# audio_chip_v2.net
KiCad netlist of a schematic drawn in EasyEDA
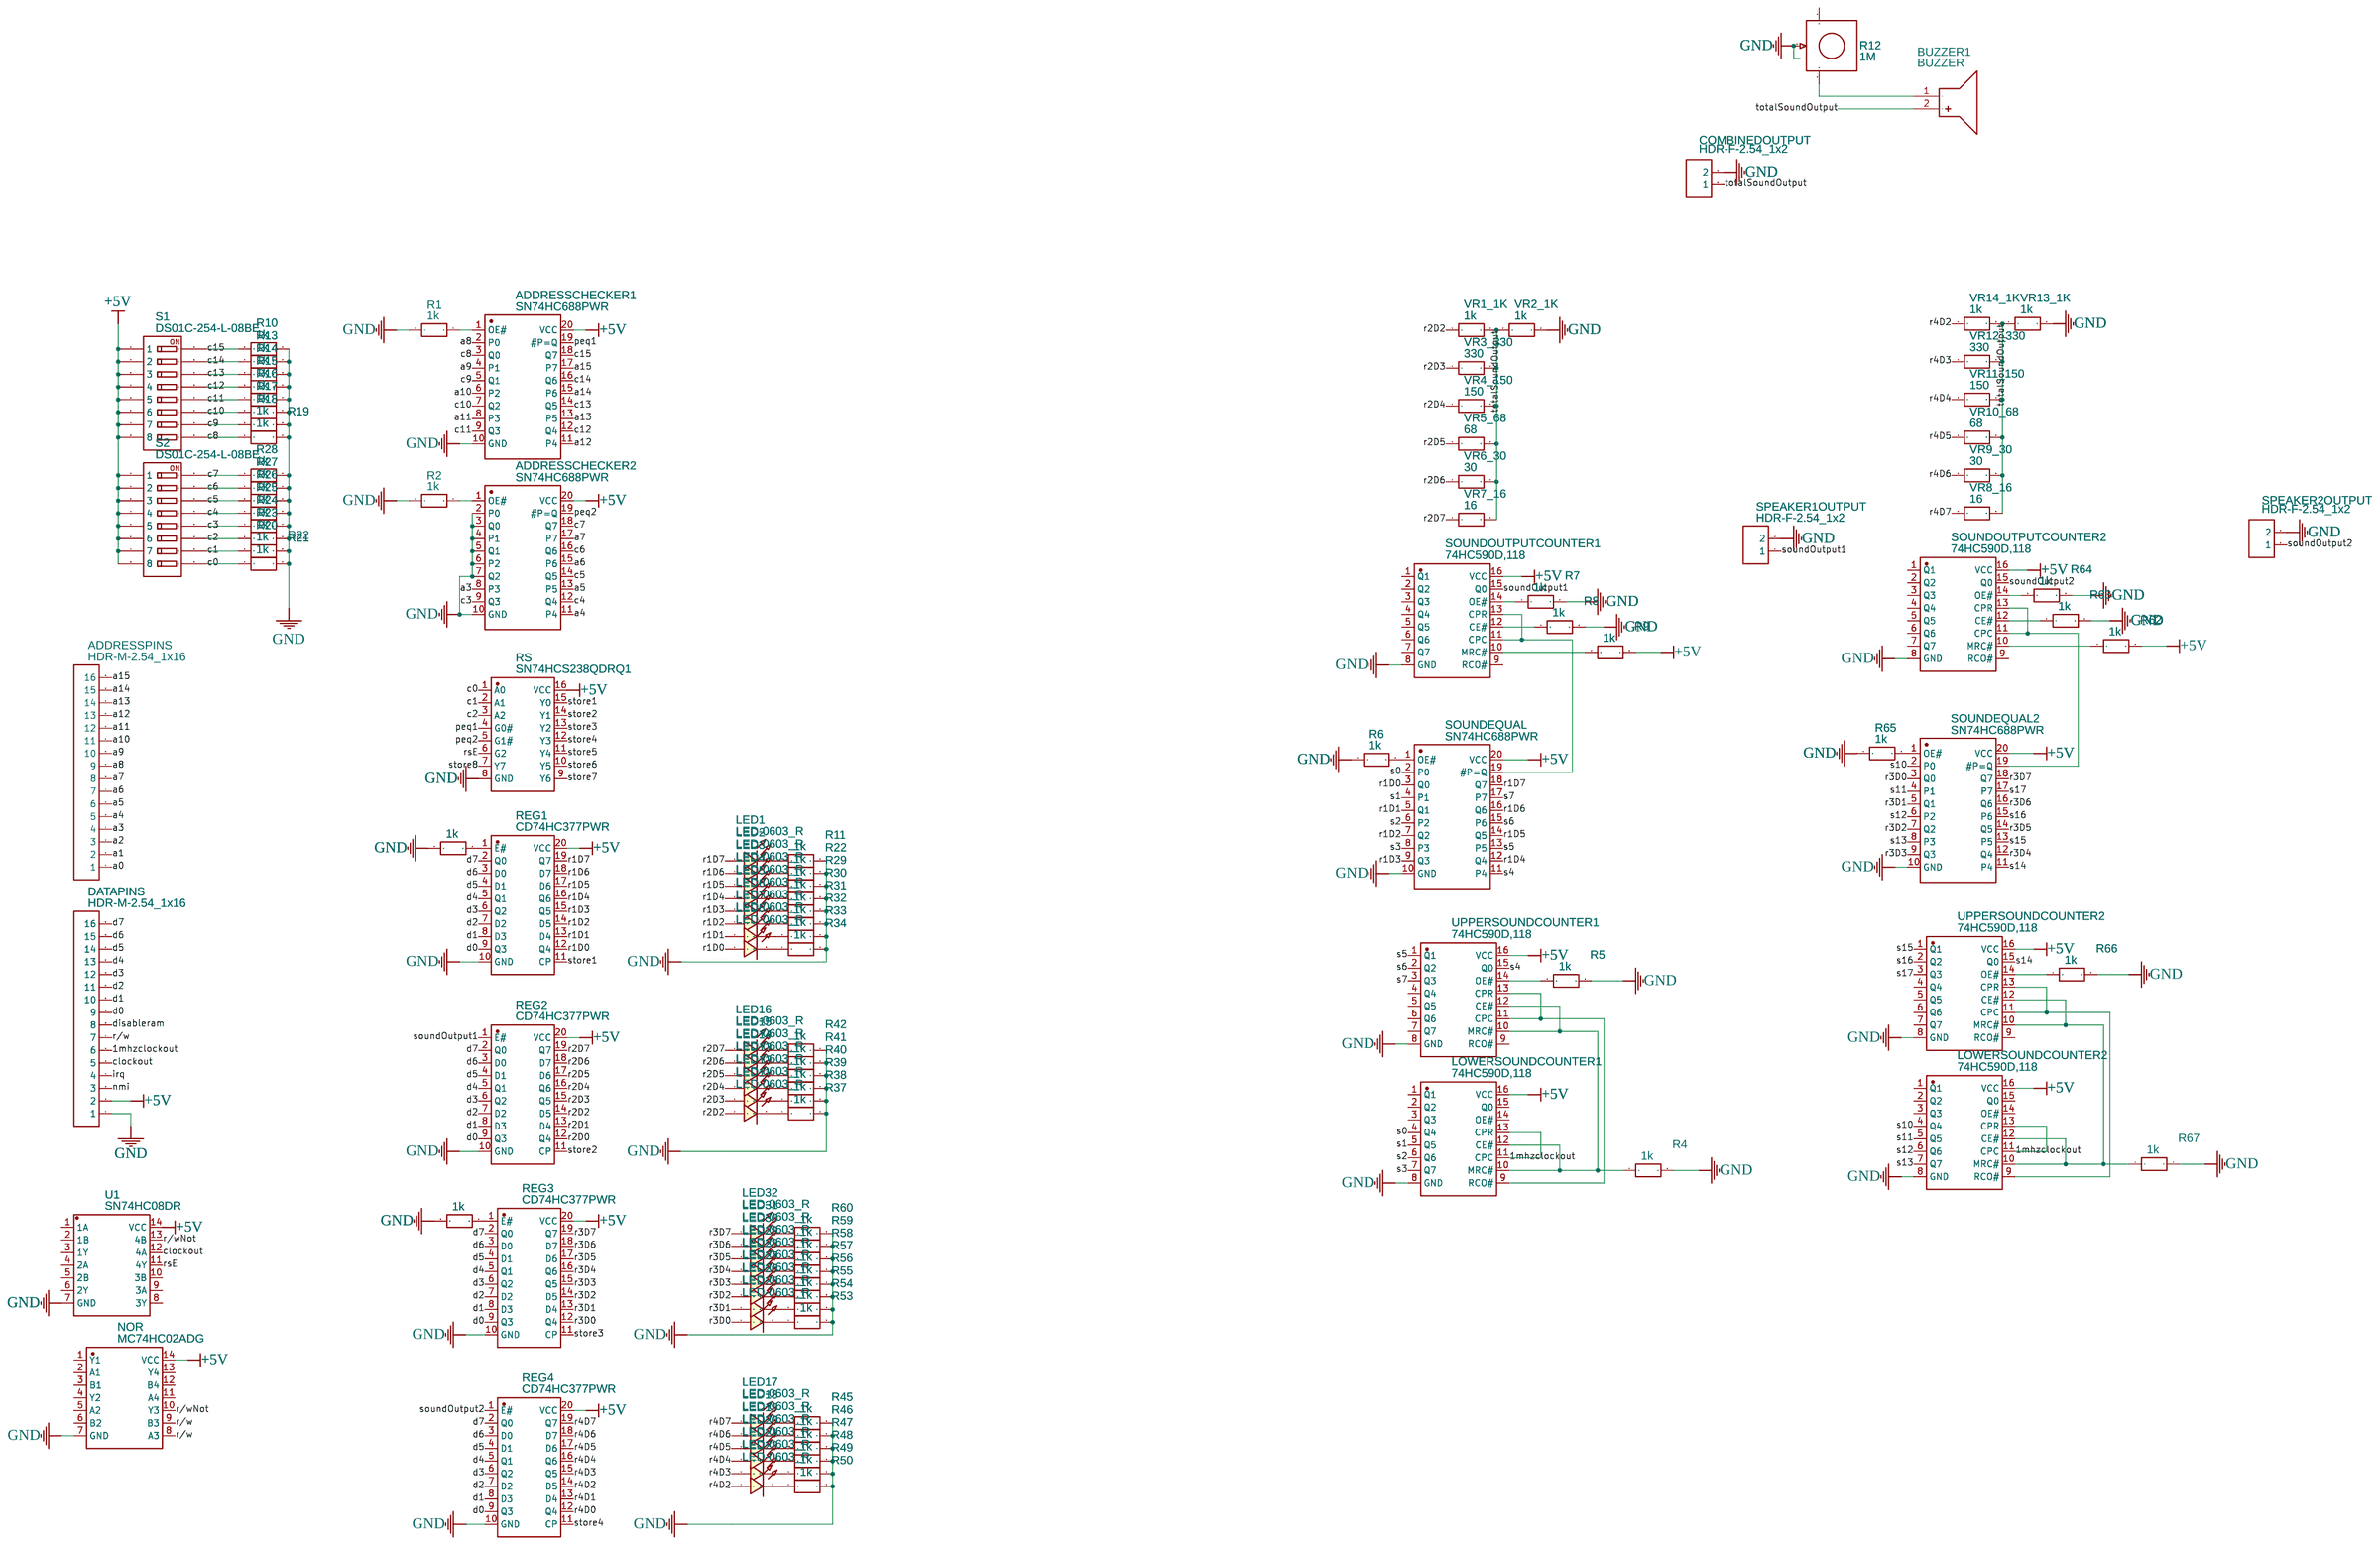
[diagram p0: schematic sheet]

(export (version "E")
  (design (tool "Eeschema 10.0.6"))
  (components
    (comp (ref "ADDRESSCHECKER1")
      (value "SN74HC688PWR")
      (fields (field (name "Manufacturer") "TI(德州仪器)"))
      (libsource (lib "") (part "SN74HC688PWR"))
    )
    (comp (ref "ADDRESSCHECKER2")
      (value "SN74HC688PWR")
      (fields (field (name "Manufacturer") "TI(德州仪器)"))
      (libsource (lib "") (part "SN74HC688PWR"))
    )
    (comp (ref "ADDRESSPINS") (value "HDR-M-2.54_1x16") (libsource (lib "") (part "HDR-M-2.54_1x16")))
    (comp (ref "BUZZER1")
      (value "BUZZER")
      (fields (field (name "Manufacturer Part") "buzzer"))
      (libsource (lib "") (part "BUZZER"))
    )
    (comp (ref "COMBINEDOUTPUT") (value "HDR-F-2.54_1x2") (libsource (lib "") (part "HDR-F-2.54_1x2_1")))
    (comp (ref "DATAPINS") (value "HDR-M-2.54_1x16") (libsource (lib "") (part "HDR-M-2.54_1x16_1")))
    (comp (ref "LED1")
      (value "LED-0603_R")
      (fields
        (field (name "Manufacturer Part") "19-217/R6C-AL1M2VY/3T")
        (field (name "Manufacturer") "EVERLIGHT(台湾亿光)")
      )
      (libsource (lib "") (part "LED-0603_R"))
    )
    (comp (ref "LED2")
      (value "LED-0603_R")
      (fields
        (field (name "Manufacturer Part") "19-217/R6C-AL1M2VY/3T")
        (field (name "Manufacturer") "EVERLIGHT(台湾亿光)")
      )
      (libsource (lib "") (part "LED-0603_R"))
    )
    (comp (ref "LED3")
      (value "LED-0603_R")
      (fields
        (field (name "Manufacturer Part") "19-217/R6C-AL1M2VY/3T")
        (field (name "Manufacturer") "EVERLIGHT(台湾亿光)")
      )
      (libsource (lib "") (part "LED-0603_R"))
    )
    (comp (ref "LED4")
      (value "LED-0603_R")
      (fields
        (field (name "Manufacturer Part") "19-217/R6C-AL1M2VY/3T")
        (field (name "Manufacturer") "EVERLIGHT(台湾亿光)")
      )
      (libsource (lib "") (part "LED-0603_R"))
    )
    (comp (ref "LED5")
      (value "LED-0603_R")
      (fields
        (field (name "Manufacturer Part") "19-217/R6C-AL1M2VY/3T")
        (field (name "Manufacturer") "EVERLIGHT(台湾亿光)")
      )
      (libsource (lib "") (part "LED-0603_R"))
    )
    (comp (ref "LED6")
      (value "LED-0603_R")
      (fields
        (field (name "Manufacturer Part") "19-217/R6C-AL1M2VY/3T")
        (field (name "Manufacturer") "EVERLIGHT(台湾亿光)")
      )
      (libsource (lib "") (part "LED-0603_R"))
    )
    (comp (ref "LED7")
      (value "LED-0603_R")
      (fields
        (field (name "Manufacturer Part") "19-217/R6C-AL1M2VY/3T")
        (field (name "Manufacturer") "EVERLIGHT(台湾亿光)")
      )
      (libsource (lib "") (part "LED-0603_R"))
    )
    (comp (ref "LED8")
      (value "LED-0603_R")
      (fields
        (field (name "Manufacturer Part") "19-217/R6C-AL1M2VY/3T")
        (field (name "Manufacturer") "EVERLIGHT(台湾亿光)")
      )
      (libsource (lib "") (part "LED-0603_R"))
    )
    (comp (ref "LED11")
      (value "LED-0603_R")
      (fields
        (field (name "Manufacturer Part") "19-217/R6C-AL1M2VY/3T")
        (field (name "Manufacturer") "EVERLIGHT(台湾亿光)")
      )
      (libsource (lib "") (part "LED-0603_R"))
    )
    (comp (ref "LED12")
      (value "LED-0603_R")
      (fields
        (field (name "Manufacturer Part") "19-217/R6C-AL1M2VY/3T")
        (field (name "Manufacturer") "EVERLIGHT(台湾亿光)")
      )
      (libsource (lib "") (part "LED-0603_R"))
    )
    (comp (ref "LED13")
      (value "LED-0603_R")
      (fields
        (field (name "Manufacturer Part") "19-217/R6C-AL1M2VY/3T")
        (field (name "Manufacturer") "EVERLIGHT(台湾亿光)")
      )
      (libsource (lib "") (part "LED-0603_R"))
    )
    (comp (ref "LED14")
      (value "LED-0603_R")
      (fields
        (field (name "Manufacturer Part") "19-217/R6C-AL1M2VY/3T")
        (field (name "Manufacturer") "EVERLIGHT(台湾亿光)")
      )
      (libsource (lib "") (part "LED-0603_R"))
    )
    (comp (ref "LED15")
      (value "LED-0603_R")
      (fields
        (field (name "Manufacturer Part") "19-217/R6C-AL1M2VY/3T")
        (field (name "Manufacturer") "EVERLIGHT(台湾亿光)")
      )
      (libsource (lib "") (part "LED-0603_R"))
    )
    (comp (ref "LED16")
      (value "LED-0603_R")
      (fields
        (field (name "Manufacturer Part") "19-217/R6C-AL1M2VY/3T")
        (field (name "Manufacturer") "EVERLIGHT(台湾亿光)")
      )
      (libsource (lib "") (part "LED-0603_R"))
    )
    (comp (ref "LED17")
      (value "LED-0603_R")
      (fields
        (field (name "Manufacturer Part") "19-217/R6C-AL1M2VY/3T")
        (field (name "Manufacturer") "EVERLIGHT(台湾亿光)")
      )
      (libsource (lib "") (part "LED-0603_R"))
    )
    (comp (ref "LED18")
      (value "LED-0603_R")
      (fields
        (field (name "Manufacturer Part") "19-217/R6C-AL1M2VY/3T")
        (field (name "Manufacturer") "EVERLIGHT(台湾亿光)")
      )
      (libsource (lib "") (part "LED-0603_R"))
    )
    (comp (ref "LED19")
      (value "LED-0603_R")
      (fields
        (field (name "Manufacturer Part") "19-217/R6C-AL1M2VY/3T")
        (field (name "Manufacturer") "EVERLIGHT(台湾亿光)")
      )
      (libsource (lib "") (part "LED-0603_R"))
    )
    (comp (ref "LED20")
      (value "LED-0603_R")
      (fields
        (field (name "Manufacturer Part") "19-217/R6C-AL1M2VY/3T")
        (field (name "Manufacturer") "EVERLIGHT(台湾亿光)")
      )
      (libsource (lib "") (part "LED-0603_R"))
    )
    (comp (ref "LED21")
      (value "LED-0603_R")
      (fields
        (field (name "Manufacturer Part") "19-217/R6C-AL1M2VY/3T")
        (field (name "Manufacturer") "EVERLIGHT(台湾亿光)")
      )
      (libsource (lib "") (part "LED-0603_R"))
    )
    (comp (ref "LED22")
      (value "LED-0603_R")
      (fields
        (field (name "Manufacturer Part") "19-217/R6C-AL1M2VY/3T")
        (field (name "Manufacturer") "EVERLIGHT(台湾亿光)")
      )
      (libsource (lib "") (part "LED-0603_R"))
    )
    (comp (ref "LED25")
      (value "LED-0603_R")
      (fields
        (field (name "Manufacturer Part") "19-217/R6C-AL1M2VY/3T")
        (field (name "Manufacturer") "EVERLIGHT(台湾亿光)")
      )
      (libsource (lib "") (part "LED-0603_R"))
    )
    (comp (ref "LED26")
      (value "LED-0603_R")
      (fields
        (field (name "Manufacturer Part") "19-217/R6C-AL1M2VY/3T")
        (field (name "Manufacturer") "EVERLIGHT(台湾亿光)")
      )
      (libsource (lib "") (part "LED-0603_R"))
    )
    (comp (ref "LED27")
      (value "LED-0603_R")
      (fields
        (field (name "Manufacturer Part") "19-217/R6C-AL1M2VY/3T")
        (field (name "Manufacturer") "EVERLIGHT(台湾亿光)")
      )
      (libsource (lib "") (part "LED-0603_R"))
    )
    (comp (ref "LED28")
      (value "LED-0603_R")
      (fields
        (field (name "Manufacturer Part") "19-217/R6C-AL1M2VY/3T")
        (field (name "Manufacturer") "EVERLIGHT(台湾亿光)")
      )
      (libsource (lib "") (part "LED-0603_R"))
    )
    (comp (ref "LED29")
      (value "LED-0603_R")
      (fields
        (field (name "Manufacturer Part") "19-217/R6C-AL1M2VY/3T")
        (field (name "Manufacturer") "EVERLIGHT(台湾亿光)")
      )
      (libsource (lib "") (part "LED-0603_R"))
    )
    (comp (ref "LED30")
      (value "LED-0603_R")
      (fields
        (field (name "Manufacturer Part") "19-217/R6C-AL1M2VY/3T")
        (field (name "Manufacturer") "EVERLIGHT(台湾亿光)")
      )
      (libsource (lib "") (part "LED-0603_R"))
    )
    (comp (ref "LED31")
      (value "LED-0603_R")
      (fields
        (field (name "Manufacturer Part") "19-217/R6C-AL1M2VY/3T")
        (field (name "Manufacturer") "EVERLIGHT(台湾亿光)")
      )
      (libsource (lib "") (part "LED-0603_R"))
    )
    (comp (ref "LED32")
      (value "LED-0603_R")
      (fields
        (field (name "Manufacturer Part") "19-217/R6C-AL1M2VY/3T")
        (field (name "Manufacturer") "EVERLIGHT(台湾亿光)")
      )
      (libsource (lib "") (part "LED-0603_R"))
    )
    (comp (ref "LOWERSOUNDCOUNTER1")
      (value "74HC590D,118")
      (fields (field (name "Manufacturer") "Nexperia(安世)"))
      (libsource (lib "") (part "74HC590D,118"))
    )
    (comp (ref "LOWERSOUNDCOUNTER2")
      (value "74HC590D,118")
      (fields (field (name "Manufacturer") "Nexperia(安世)"))
      (libsource (lib "") (part "74HC590D,118"))
    )
    (comp (ref "NOR")
      (value "MC74HC02ADG")
      (fields (field (name "Manufacturer") "onsemi(安森美)"))
      (libsource (lib "") (part "MC74HC02ADG"))
    )
    (comp (ref "R1") (value "1k") (libsource (lib "") (part "R_1206_EU_2")))
    (comp (ref "R2") (value "1k") (libsource (lib "") (part "R_1206_EU_2")))
    (comp (ref "R3") (value "1k") (libsource (lib "") (part "R_1206_EU_2")))
    (comp (ref "R4") (value "1k") (libsource (lib "") (part "R_1206_EU_2")))
    (comp (ref "R5") (value "1k") (libsource (lib "") (part "R_1206_EU_2")))
    (comp (ref "R6") (value "1k") (libsource (lib "") (part "R_1206_EU_2")))
    (comp (ref "R7") (value "1k") (libsource (lib "") (part "R_1206_EU_2")))
    (comp (ref "R8") (value "1k") (libsource (lib "") (part "R_1206_EU_2")))
    (comp (ref "R9") (value "1k") (libsource (lib "") (part "R_1206_EU_2")))
    (comp (ref "R10") (value "1k") (libsource (lib "") (part "R_1206_EU_2")))
    (comp (ref "R11") (value "1k") (libsource (lib "") (part "R_1206_EU_2")))
    (comp (ref "R12")
      (value "1M")
      (fields
        (field (name "Manufacturer Part") "3386T-1-LS1MEG(105)")
        (field (name "Manufacturer") "Jameco ValuePro")
      )
      (libsource (lib "") (part "3/8 Inch Square Cermet Potentiometer 1MEG Ohms 1/2 Watt 1 Turn Thru Hole"))
    )
    (comp (ref "R13") (value "1k") (libsource (lib "") (part "R_1206_EU_2")))
    (comp (ref "R14") (value "1k") (libsource (lib "") (part "R_1206_EU_2")))
    (comp (ref "R15") (value "1k") (libsource (lib "") (part "R_1206_EU_2")))
    (comp (ref "R16") (value "1k") (libsource (lib "") (part "R_1206_EU_2")))
    (comp (ref "R17") (value "1k") (libsource (lib "") (part "R_1206_EU_2")))
    (comp (ref "R18") (value "1k") (libsource (lib "") (part "R_1206_EU_2")))
    (comp (ref "R19") (value "1k") (libsource (lib "") (part "R_1206_EU_2")))
    (comp (ref "R20") (value "1k") (libsource (lib "") (part "R_1206_EU_2")))
    (comp (ref "R21") (value "1k") (libsource (lib "") (part "R_1206_EU_2")))
    (comp (ref "R22") (value "1k") (libsource (lib "") (part "R_1206_EU_2")))
    (comp (ref "R23") (value "1k") (libsource (lib "") (part "R_1206_EU_2")))
    (comp (ref "R24") (value "1k") (libsource (lib "") (part "R_1206_EU_2")))
    (comp (ref "R25") (value "1k") (libsource (lib "") (part "R_1206_EU_2")))
    (comp (ref "R26") (value "1k") (libsource (lib "") (part "R_1206_EU_2")))
    (comp (ref "R27") (value "1k") (libsource (lib "") (part "R_1206_EU_2")))
    (comp (ref "R28") (value "1k") (libsource (lib "") (part "R_1206_EU_2")))
    (comp (ref "R29") (value "1k") (libsource (lib "") (part "R_1206_EU_2")))
    (comp (ref "R30") (value "1k") (libsource (lib "") (part "R_1206_EU_2")))
    (comp (ref "R31") (value "1k") (libsource (lib "") (part "R_1206_EU_2")))
    (comp (ref "R32") (value "1k") (libsource (lib "") (part "R_1206_EU_2")))
    (comp (ref "R33") (value "1k") (libsource (lib "") (part "R_1206_EU_2")))
    (comp (ref "R34") (value "1k") (libsource (lib "") (part "R_1206_EU_2")))
    (comp (ref "R37") (value "1k") (libsource (lib "") (part "R_1206_EU_2")))
    (comp (ref "R38") (value "1k") (libsource (lib "") (part "R_1206_EU_2")))
    (comp (ref "R39") (value "1k") (libsource (lib "") (part "R_1206_EU_2")))
    (comp (ref "R40") (value "1k") (libsource (lib "") (part "R_1206_EU_2")))
    (comp (ref "R41") (value "1k") (libsource (lib "") (part "R_1206_EU_2")))
    (comp (ref "R42") (value "1k") (libsource (lib "") (part "R_1206_EU_2")))
    (comp (ref "R45") (value "1k") (libsource (lib "") (part "R_1206_EU_2")))
    (comp (ref "R46") (value "1k") (libsource (lib "") (part "R_1206_EU_2")))
    (comp (ref "R47") (value "1k") (libsource (lib "") (part "R_1206_EU_2")))
    (comp (ref "R48") (value "1k") (libsource (lib "") (part "R_1206_EU_2")))
    (comp (ref "R49") (value "1k") (libsource (lib "") (part "R_1206_EU_2")))
    (comp (ref "R50") (value "1k") (libsource (lib "") (part "R_1206_EU_2")))
    (comp (ref "R53") (value "1k") (libsource (lib "") (part "R_1206_EU_2")))
    (comp (ref "R54") (value "1k") (libsource (lib "") (part "R_1206_EU_2")))
    (comp (ref "R55") (value "1k") (libsource (lib "") (part "R_1206_EU_2")))
    (comp (ref "R56") (value "1k") (libsource (lib "") (part "R_1206_EU_2")))
    (comp (ref "R57") (value "1k") (libsource (lib "") (part "R_1206_EU_2")))
    (comp (ref "R58") (value "1k") (libsource (lib "") (part "R_1206_EU_2")))
    (comp (ref "R59") (value "1k") (libsource (lib "") (part "R_1206_EU_2")))
    (comp (ref "R60") (value "1k") (libsource (lib "") (part "R_1206_EU_2")))
    (comp (ref "R61") (value "1k") (libsource (lib "") (part "R_1206_EU_2")))
    (comp (ref "R62") (value "1k") (libsource (lib "") (part "R_1206_EU_2")))
    (comp (ref "R63") (value "1k") (libsource (lib "") (part "R_1206_EU_2")))
    (comp (ref "R64") (value "1k") (libsource (lib "") (part "R_1206_EU_2")))
    (comp (ref "R65") (value "1k") (libsource (lib "") (part "R_1206_EU_2")))
    (comp (ref "R66") (value "1k") (libsource (lib "") (part "R_1206_EU_2")))
    (comp (ref "R67") (value "1k") (libsource (lib "") (part "R_1206_EU_2")))
    (comp (ref "REG1")
      (value "CD74HC377PWR")
      (fields (field (name "Manufacturer") "TI(德州仪器)"))
      (libsource (lib "") (part "CD74HC377PWR"))
    )
    (comp (ref "REG2")
      (value "CD74HC377PWR")
      (fields (field (name "Manufacturer") "TI(德州仪器)"))
      (libsource (lib "") (part "CD74HC377PWR"))
    )
    (comp (ref "REG3")
      (value "CD74HC377PWR")
      (fields (field (name "Manufacturer") "TI(德州仪器)"))
      (libsource (lib "") (part "CD74HC377PWR"))
    )
    (comp (ref "REG4")
      (value "CD74HC377PWR")
      (fields (field (name "Manufacturer") "TI(德州仪器)"))
      (libsource (lib "") (part "CD74HC377PWR"))
    )
    (comp (ref "RS")
      (value "SN74HCS238QDRQ1")
      (fields (field (name "Manufacturer") "TI(德州仪器)"))
      (libsource (lib "") (part "SN74HCS238QDRQ1"))
    )
    (comp (ref "S1")
      (value "DS01C-254-L-08BE")
      (fields
        (field (name "Manufacturer Part") "DS01C-254-L-07BE")
        (field (name "Manufacturer") "CUI Devices")
      )
      (libsource (lib "") (part "DS01C-254-L-08BE"))
    )
    (comp (ref "S2")
      (value "DS01C-254-L-08BE")
      (fields
        (field (name "Manufacturer Part") "DS01C-254-L-07BE")
        (field (name "Manufacturer") "CUI Devices")
      )
      (libsource (lib "") (part "DS01C-254-L-08BE"))
    )
    (comp (ref "SOUNDEQUAL")
      (value "SN74HC688PWR")
      (fields (field (name "Manufacturer") "TI(德州仪器)"))
      (libsource (lib "") (part "SN74HC688PWR_1"))
    )
    (comp (ref "SOUNDEQUAL2")
      (value "SN74HC688PWR")
      (fields (field (name "Manufacturer") "TI(德州仪器)"))
      (libsource (lib "") (part "SN74HC688PWR_1"))
    )
    (comp (ref "SOUNDOUTPUTCOUNTER1")
      (value "74HC590D,118")
      (fields (field (name "Manufacturer") "Nexperia(安世)"))
      (libsource (lib "") (part "74HC590D,118_1"))
    )
    (comp (ref "SOUNDOUTPUTCOUNTER2")
      (value "74HC590D,118")
      (fields (field (name "Manufacturer") "Nexperia(安世)"))
      (libsource (lib "") (part "74HC590D,118_1"))
    )
    (comp (ref "SPEAKER1OUTPUT") (value "HDR-F-2.54_1x2") (libsource (lib "") (part "HDR-F-2.54_1x2_2")))
    (comp (ref "SPEAKER2OUTPUT") (value "HDR-F-2.54_1x2") (libsource (lib "") (part "HDR-F-2.54_1x2")))
    (comp (ref "U1")
      (value "SN74HC08DR")
      (fields (field (name "Manufacturer") "TI(德州仪器)"))
      (libsource (lib "") (part "SN74HC08DR"))
    )
    (comp (ref "UPPERSOUNDCOUNTER1")
      (value "74HC590D,118")
      (fields (field (name "Manufacturer") "Nexperia(安世)"))
      (libsource (lib "") (part "74HC590D,118_2"))
    )
    (comp (ref "UPPERSOUNDCOUNTER2")
      (value "74HC590D,118")
      (fields (field (name "Manufacturer") "Nexperia(安世)"))
      (libsource (lib "") (part "74HC590D,118_2"))
    )
    (comp (ref "VR1_1K") (value "1k") (libsource (lib "") (part "R_1206_EU_9")))
    (comp (ref "VR2_1K") (value "1k") (libsource (lib "") (part "R_1206_EU_6")))
    (comp (ref "VR3_330") (value "330") (libsource (lib "") (part "R_1206_EU_8")))
    (comp (ref "VR4_150") (value "150") (libsource (lib "") (part "R_1206_EU_7")))
    (comp (ref "VR5_68") (value "68") (libsource (lib "") (part "R_1206_EU_11")))
    (comp (ref "VR6_30") (value "30") (libsource (lib "") (part "R_1206_EU_14")))
    (comp (ref "VR7_16") (value "16") (libsource (lib "") (part "R_1206_EU_13")))
    (comp (ref "VR8_16") (value "16") (libsource (lib "") (part "R_1206_EU_3")))
    (comp (ref "VR9_30") (value "30") (libsource (lib "") (part "R_1206_EU_4")))
    (comp (ref "VR10_68") (value "68") (libsource (lib "") (part "R_1206_EU_5")))
    (comp (ref "VR11_150") (value "150") (libsource (lib "") (part "R_1206_EU_12")))
    (comp (ref "VR12_330") (value "330") (libsource (lib "") (part "R_1206_EU_10")))
    (comp (ref "VR13_1K") (value "1k") (libsource (lib "") (part "R_1206_EU_1")))
    (comp (ref "VR14_1K") (value "1k") (libsource (lib "") (part "R_1206_EU")))
  )
  (nets
    (net (code "1") (name "+5V") (class "Default")
      (node (ref "ADDRESSCHECKER1") (pin "20") (pinfunction "VCC_20") (pintype "unspecified"))
      (node (ref "ADDRESSCHECKER2") (pin "20") (pinfunction "VCC_20") (pintype "unspecified"))
      (node (ref "DATAPINS") (pin "2") (pinfunction "2_2") (pintype "unspecified"))
      (node (ref "LOWERSOUNDCOUNTER1") (pin "16") (pinfunction "VCC_16") (pintype "unspecified"))
      (node (ref "LOWERSOUNDCOUNTER2") (pin "16") (pinfunction "VCC_16") (pintype "unspecified"))
      (node (ref "NOR") (pin "14") (pinfunction "VCC_14") (pintype "unspecified"))
      (node (ref "R62") (pin "2") (pinfunction "2_2") (pintype "unspecified"))
      (node (ref "R9") (pin "2") (pinfunction "2_2") (pintype "unspecified"))
      (node (ref "REG1") (pin "20") (pinfunction "VCC_20") (pintype "unspecified"))
      (node (ref "REG2") (pin "20") (pinfunction "VCC_20") (pintype "unspecified"))
      (node (ref "REG3") (pin "20") (pinfunction "VCC_20") (pintype "unspecified"))
      (node (ref "REG4") (pin "20") (pinfunction "VCC_20") (pintype "unspecified"))
      (node (ref "RS") (pin "16") (pinfunction "VCC_16") (pintype "unspecified"))
      (node (ref "S1") (pin "1") (pinfunction "1_1") (pintype "unspecified"))
      (node (ref "S1") (pin "2") (pinfunction "2_2") (pintype "unspecified"))
      (node (ref "S1") (pin "3") (pinfunction "3_3") (pintype "unspecified"))
      (node (ref "S1") (pin "4") (pinfunction "4_4") (pintype "unspecified"))
      (node (ref "S1") (pin "5") (pinfunction "5_5") (pintype "unspecified"))
      (node (ref "S1") (pin "6") (pinfunction "6_6") (pintype "unspecified"))
      (node (ref "S1") (pin "7") (pinfunction "7_7") (pintype "unspecified"))
      (node (ref "S1") (pin "8") (pinfunction "8_8") (pintype "unspecified"))
      (node (ref "S2") (pin "1") (pinfunction "1_1") (pintype "unspecified"))
      (node (ref "S2") (pin "2") (pinfunction "2_2") (pintype "unspecified"))
      (node (ref "S2") (pin "3") (pinfunction "3_3") (pintype "unspecified"))
      (node (ref "S2") (pin "4") (pinfunction "4_4") (pintype "unspecified"))
      (node (ref "S2") (pin "5") (pinfunction "5_5") (pintype "unspecified"))
      (node (ref "S2") (pin "6") (pinfunction "6_6") (pintype "unspecified"))
      (node (ref "S2") (pin "7") (pinfunction "7_7") (pintype "unspecified"))
      (node (ref "S2") (pin "8") (pinfunction "8_8") (pintype "unspecified"))
      (node (ref "SOUNDEQUAL") (pin "20") (pinfunction "VCC_20") (pintype "unspecified"))
      (node (ref "SOUNDEQUAL2") (pin "20") (pinfunction "VCC_20") (pintype "unspecified"))
      (node (ref "SOUNDOUTPUTCOUNTER1") (pin "16") (pinfunction "VCC_16") (pintype "unspecified"))
      (node (ref "SOUNDOUTPUTCOUNTER2") (pin "16") (pinfunction "VCC_16") (pintype "unspecified"))
      (node (ref "U1") (pin "14") (pinfunction "VCC_14") (pintype "unspecified"))
      (node (ref "UPPERSOUNDCOUNTER1") (pin "16") (pinfunction "VCC_16") (pintype "unspecified"))
      (node (ref "UPPERSOUNDCOUNTER2") (pin "16") (pinfunction "VCC_16") (pintype "unspecified"))
    )
    (net (code "2") (name "/1mhzclockout") (class "Default")
      (node (ref "DATAPINS") (pin "6") (pinfunction "6_6") (pintype "unspecified"))
      (node (ref "LOWERSOUNDCOUNTER1") (pin "11") (pinfunction "CPC_11") (pintype "unspecified"))
      (node (ref "LOWERSOUNDCOUNTER1") (pin "13") (pinfunction "CPR_13") (pintype "unspecified"))
      (node (ref "LOWERSOUNDCOUNTER2") (pin "11") (pinfunction "CPC_11") (pintype "unspecified"))
      (node (ref "LOWERSOUNDCOUNTER2") (pin "13") (pinfunction "CPR_13") (pintype "unspecified"))
    )
    (net (code "3") (name "/a0") (class "Default")
      (node (ref "ADDRESSPINS") (pin "1") (pinfunction "1_1") (pintype "unspecified"))
    )
    (net (code "4") (name "/a1") (class "Default")
      (node (ref "ADDRESSPINS") (pin "2") (pinfunction "2_2") (pintype "unspecified"))
    )
    (net (code "5") (name "/a2") (class "Default")
      (node (ref "ADDRESSPINS") (pin "3") (pinfunction "3_3") (pintype "unspecified"))
    )
    (net (code "6") (name "/a3") (class "Default")
      (node (ref "ADDRESSCHECKER2") (pin "8") (pinfunction "P3_8") (pintype "unspecified"))
      (node (ref "ADDRESSPINS") (pin "4") (pinfunction "4_4") (pintype "unspecified"))
    )
    (net (code "7") (name "/a4") (class "Default")
      (node (ref "ADDRESSCHECKER2") (pin "11") (pinfunction "P4_11") (pintype "unspecified"))
      (node (ref "ADDRESSPINS") (pin "5") (pinfunction "5_5") (pintype "unspecified"))
    )
    (net (code "8") (name "/a5") (class "Default")
      (node (ref "ADDRESSCHECKER2") (pin "13") (pinfunction "P5_13") (pintype "unspecified"))
      (node (ref "ADDRESSPINS") (pin "6") (pinfunction "6_6") (pintype "unspecified"))
    )
    (net (code "9") (name "/a6") (class "Default")
      (node (ref "ADDRESSCHECKER2") (pin "15") (pinfunction "P6_15") (pintype "unspecified"))
      (node (ref "ADDRESSPINS") (pin "7") (pinfunction "7_7") (pintype "unspecified"))
    )
    (net (code "10") (name "/a7") (class "Default")
      (node (ref "ADDRESSCHECKER2") (pin "17") (pinfunction "P7_17") (pintype "unspecified"))
      (node (ref "ADDRESSPINS") (pin "8") (pinfunction "8_8") (pintype "unspecified"))
    )
    (net (code "11") (name "/a8") (class "Default")
      (node (ref "ADDRESSCHECKER1") (pin "2") (pinfunction "P0_2") (pintype "unspecified"))
      (node (ref "ADDRESSPINS") (pin "9") (pinfunction "9_9") (pintype "unspecified"))
    )
    (net (code "12") (name "/a9") (class "Default")
      (node (ref "ADDRESSCHECKER1") (pin "4") (pinfunction "P1_4") (pintype "unspecified"))
      (node (ref "ADDRESSPINS") (pin "10") (pinfunction "10_10") (pintype "unspecified"))
    )
    (net (code "13") (name "/a10") (class "Default")
      (node (ref "ADDRESSCHECKER1") (pin "6") (pinfunction "P2_6") (pintype "unspecified"))
      (node (ref "ADDRESSPINS") (pin "11") (pinfunction "11_11") (pintype "unspecified"))
    )
    (net (code "14") (name "/a11") (class "Default")
      (node (ref "ADDRESSCHECKER1") (pin "8") (pinfunction "P3_8") (pintype "unspecified"))
      (node (ref "ADDRESSPINS") (pin "12") (pinfunction "12_12") (pintype "unspecified"))
    )
    (net (code "15") (name "/a12") (class "Default")
      (node (ref "ADDRESSCHECKER1") (pin "11") (pinfunction "P4_11") (pintype "unspecified"))
      (node (ref "ADDRESSPINS") (pin "13") (pinfunction "13_13") (pintype "unspecified"))
    )
    (net (code "16") (name "/a13") (class "Default")
      (node (ref "ADDRESSCHECKER1") (pin "13") (pinfunction "P5_13") (pintype "unspecified"))
      (node (ref "ADDRESSPINS") (pin "14") (pinfunction "14_14") (pintype "unspecified"))
    )
    (net (code "17") (name "/a14") (class "Default")
      (node (ref "ADDRESSCHECKER1") (pin "15") (pinfunction "P6_15") (pintype "unspecified"))
      (node (ref "ADDRESSPINS") (pin "15") (pinfunction "15_15") (pintype "unspecified"))
    )
    (net (code "18") (name "/a15") (class "Default")
      (node (ref "ADDRESSCHECKER1") (pin "17") (pinfunction "P7_17") (pintype "unspecified"))
      (node (ref "ADDRESSPINS") (pin "16") (pinfunction "16_16") (pintype "unspecified"))
    )
    (net (code "19") (name "/c0") (class "Default")
      (node (ref "R21") (pin "1") (pinfunction "1_1") (pintype "unspecified"))
      (node (ref "RS") (pin "1") (pinfunction "A0_1") (pintype "unspecified"))
      (node (ref "S2") (pin "9") (pinfunction "9_9") (pintype "unspecified"))
    )
    (net (code "20") (name "/c1") (class "Default")
      (node (ref "R20") (pin "1") (pinfunction "1_1") (pintype "unspecified"))
      (node (ref "RS") (pin "2") (pinfunction "A1_2") (pintype "unspecified"))
      (node (ref "S2") (pin "10") (pinfunction "10_10") (pintype "unspecified"))
    )
    (net (code "21") (name "/c2") (class "Default")
      (node (ref "R23") (pin "1") (pinfunction "1_1") (pintype "unspecified"))
      (node (ref "RS") (pin "3") (pinfunction "A2_3") (pintype "unspecified"))
      (node (ref "S2") (pin "11") (pinfunction "11_11") (pintype "unspecified"))
    )
    (net (code "22") (name "/c3") (class "Default")
      (node (ref "ADDRESSCHECKER2") (pin "9") (pinfunction "Q3_9") (pintype "unspecified"))
      (node (ref "R24") (pin "1") (pinfunction "1_1") (pintype "unspecified"))
      (node (ref "S2") (pin "12") (pinfunction "12_12") (pintype "unspecified"))
    )
    (net (code "23") (name "/c4") (class "Default")
      (node (ref "ADDRESSCHECKER2") (pin "12") (pinfunction "Q4_12") (pintype "unspecified"))
      (node (ref "R25") (pin "1") (pinfunction "1_1") (pintype "unspecified"))
      (node (ref "S2") (pin "13") (pinfunction "13_13") (pintype "unspecified"))
    )
    (net (code "24") (name "/c5") (class "Default")
      (node (ref "ADDRESSCHECKER2") (pin "14") (pinfunction "Q5_14") (pintype "unspecified"))
      (node (ref "R26") (pin "1") (pinfunction "1_1") (pintype "unspecified"))
      (node (ref "S2") (pin "14") (pinfunction "14_14") (pintype "unspecified"))
    )
    (net (code "25") (name "/c6") (class "Default")
      (node (ref "ADDRESSCHECKER2") (pin "16") (pinfunction "Q6_16") (pintype "unspecified"))
      (node (ref "R27") (pin "1") (pinfunction "1_1") (pintype "unspecified"))
      (node (ref "S2") (pin "15") (pinfunction "15_15") (pintype "unspecified"))
    )
    (net (code "26") (name "/c7") (class "Default")
      (node (ref "ADDRESSCHECKER2") (pin "18") (pinfunction "Q7_18") (pintype "unspecified"))
      (node (ref "R28") (pin "1") (pinfunction "1_1") (pintype "unspecified"))
      (node (ref "S2") (pin "16") (pinfunction "16_16") (pintype "unspecified"))
    )
    (net (code "27") (name "/c8") (class "Default")
      (node (ref "ADDRESSCHECKER1") (pin "3") (pinfunction "Q0_3") (pintype "unspecified"))
      (node (ref "R19") (pin "1") (pinfunction "1_1") (pintype "unspecified"))
      (node (ref "S1") (pin "9") (pinfunction "9_9") (pintype "unspecified"))
    )
    (net (code "28") (name "/c9") (class "Default")
      (node (ref "ADDRESSCHECKER1") (pin "5") (pinfunction "Q1_5") (pintype "unspecified"))
      (node (ref "R18") (pin "1") (pinfunction "1_1") (pintype "unspecified"))
      (node (ref "S1") (pin "10") (pinfunction "10_10") (pintype "unspecified"))
    )
    (net (code "29") (name "/c10") (class "Default")
      (node (ref "ADDRESSCHECKER1") (pin "7") (pinfunction "Q2_7") (pintype "unspecified"))
      (node (ref "R17") (pin "1") (pinfunction "1_1") (pintype "unspecified"))
      (node (ref "S1") (pin "11") (pinfunction "11_11") (pintype "unspecified"))
    )
    (net (code "30") (name "/c11") (class "Default")
      (node (ref "ADDRESSCHECKER1") (pin "9") (pinfunction "Q3_9") (pintype "unspecified"))
      (node (ref "R16") (pin "1") (pinfunction "1_1") (pintype "unspecified"))
      (node (ref "S1") (pin "12") (pinfunction "12_12") (pintype "unspecified"))
    )
    (net (code "31") (name "/c12") (class "Default")
      (node (ref "ADDRESSCHECKER1") (pin "12") (pinfunction "Q4_12") (pintype "unspecified"))
      (node (ref "R15") (pin "1") (pinfunction "1_1") (pintype "unspecified"))
      (node (ref "S1") (pin "13") (pinfunction "13_13") (pintype "unspecified"))
    )
    (net (code "32") (name "/c13") (class "Default")
      (node (ref "ADDRESSCHECKER1") (pin "14") (pinfunction "Q5_14") (pintype "unspecified"))
      (node (ref "R14") (pin "1") (pinfunction "1_1") (pintype "unspecified"))
      (node (ref "S1") (pin "14") (pinfunction "14_14") (pintype "unspecified"))
    )
    (net (code "33") (name "/c14") (class "Default")
      (node (ref "ADDRESSCHECKER1") (pin "16") (pinfunction "Q6_16") (pintype "unspecified"))
      (node (ref "R13") (pin "1") (pinfunction "1_1") (pintype "unspecified"))
      (node (ref "S1") (pin "15") (pinfunction "15_15") (pintype "unspecified"))
    )
    (net (code "34") (name "/c15") (class "Default")
      (node (ref "ADDRESSCHECKER1") (pin "18") (pinfunction "Q7_18") (pintype "unspecified"))
      (node (ref "R10") (pin "1") (pinfunction "1_1") (pintype "unspecified"))
      (node (ref "S1") (pin "16") (pinfunction "16_16") (pintype "unspecified"))
    )
    (net (code "35") (name "/clockout") (class "Default")
      (node (ref "DATAPINS") (pin "5") (pinfunction "5_5") (pintype "unspecified"))
      (node (ref "U1") (pin "12") (pinfunction "4A_12") (pintype "unspecified"))
    )
    (net (code "36") (name "/d0") (class "Default")
      (node (ref "DATAPINS") (pin "9") (pinfunction "9_9") (pintype "unspecified"))
      (node (ref "REG1") (pin "9") (pinfunction "Q3_9") (pintype "unspecified"))
      (node (ref "REG2") (pin "9") (pinfunction "Q3_9") (pintype "unspecified"))
      (node (ref "REG3") (pin "9") (pinfunction "Q3_9") (pintype "unspecified"))
      (node (ref "REG4") (pin "9") (pinfunction "Q3_9") (pintype "unspecified"))
    )
    (net (code "37") (name "/d1") (class "Default")
      (node (ref "DATAPINS") (pin "10") (pinfunction "10_10") (pintype "unspecified"))
      (node (ref "REG1") (pin "8") (pinfunction "D3_8") (pintype "unspecified"))
      (node (ref "REG2") (pin "8") (pinfunction "D3_8") (pintype "unspecified"))
      (node (ref "REG3") (pin "8") (pinfunction "D3_8") (pintype "unspecified"))
      (node (ref "REG4") (pin "8") (pinfunction "D3_8") (pintype "unspecified"))
    )
    (net (code "38") (name "/d2") (class "Default")
      (node (ref "DATAPINS") (pin "11") (pinfunction "11_11") (pintype "unspecified"))
      (node (ref "REG1") (pin "7") (pinfunction "D2_7") (pintype "unspecified"))
      (node (ref "REG2") (pin "7") (pinfunction "D2_7") (pintype "unspecified"))
      (node (ref "REG3") (pin "7") (pinfunction "D2_7") (pintype "unspecified"))
      (node (ref "REG4") (pin "7") (pinfunction "D2_7") (pintype "unspecified"))
    )
    (net (code "39") (name "/d3") (class "Default")
      (node (ref "DATAPINS") (pin "12") (pinfunction "12_12") (pintype "unspecified"))
      (node (ref "REG1") (pin "6") (pinfunction "Q2_6") (pintype "unspecified"))
      (node (ref "REG2") (pin "6") (pinfunction "Q2_6") (pintype "unspecified"))
      (node (ref "REG3") (pin "6") (pinfunction "Q2_6") (pintype "unspecified"))
      (node (ref "REG4") (pin "6") (pinfunction "Q2_6") (pintype "unspecified"))
    )
    (net (code "40") (name "/d4") (class "Default")
      (node (ref "DATAPINS") (pin "13") (pinfunction "13_13") (pintype "unspecified"))
      (node (ref "REG1") (pin "5") (pinfunction "Q1_5") (pintype "unspecified"))
      (node (ref "REG2") (pin "5") (pinfunction "Q1_5") (pintype "unspecified"))
      (node (ref "REG3") (pin "5") (pinfunction "Q1_5") (pintype "unspecified"))
      (node (ref "REG4") (pin "5") (pinfunction "Q1_5") (pintype "unspecified"))
    )
    (net (code "41") (name "/d5") (class "Default")
      (node (ref "DATAPINS") (pin "14") (pinfunction "14_14") (pintype "unspecified"))
      (node (ref "REG1") (pin "4") (pinfunction "D1_4") (pintype "unspecified"))
      (node (ref "REG2") (pin "4") (pinfunction "D1_4") (pintype "unspecified"))
      (node (ref "REG3") (pin "4") (pinfunction "D1_4") (pintype "unspecified"))
      (node (ref "REG4") (pin "4") (pinfunction "D1_4") (pintype "unspecified"))
    )
    (net (code "42") (name "/d6") (class "Default")
      (node (ref "DATAPINS") (pin "15") (pinfunction "15_15") (pintype "unspecified"))
      (node (ref "REG1") (pin "3") (pinfunction "D0_3") (pintype "unspecified"))
      (node (ref "REG2") (pin "3") (pinfunction "D0_3") (pintype "unspecified"))
      (node (ref "REG3") (pin "3") (pinfunction "D0_3") (pintype "unspecified"))
      (node (ref "REG4") (pin "3") (pinfunction "D0_3") (pintype "unspecified"))
    )
    (net (code "43") (name "/d7") (class "Default")
      (node (ref "DATAPINS") (pin "16") (pinfunction "16_16") (pintype "unspecified"))
      (node (ref "REG1") (pin "2") (pinfunction "Q0_2") (pintype "unspecified"))
      (node (ref "REG2") (pin "2") (pinfunction "Q0_2") (pintype "unspecified"))
      (node (ref "REG3") (pin "2") (pinfunction "Q0_2") (pintype "unspecified"))
      (node (ref "REG4") (pin "2") (pinfunction "Q0_2") (pintype "unspecified"))
    )
    (net (code "44") (name "/disableram") (class "Default")
      (node (ref "DATAPINS") (pin "8") (pinfunction "8_8") (pintype "unspecified"))
    )
    (net (code "45") (name "/irq") (class "Default")
      (node (ref "DATAPINS") (pin "4") (pinfunction "4_4") (pintype "unspecified"))
    )
    (net (code "46") (name "/nmi") (class "Default")
      (node (ref "DATAPINS") (pin "3") (pinfunction "3_3") (pintype "unspecified"))
    )
    (net (code "47") (name "/peq1") (class "Default")
      (node (ref "ADDRESSCHECKER1") (pin "19") (pinfunction "#P=Q_19") (pintype "unspecified"))
      (node (ref "RS") (pin "4") (pinfunction "G0#_4") (pintype "unspecified"))
    )
    (net (code "48") (name "/peq2") (class "Default")
      (node (ref "ADDRESSCHECKER2") (pin "19") (pinfunction "#P=Q_19") (pintype "unspecified"))
      (node (ref "RS") (pin "5") (pinfunction "G1#_5") (pintype "unspecified"))
    )
    (net (code "49") (name "/r1D0") (class "Default")
      (node (ref "LED8") (pin "1") (pinfunction "1_1") (pintype "unspecified"))
      (node (ref "REG1") (pin "12") (pinfunction "Q4_12") (pintype "unspecified"))
      (node (ref "SOUNDEQUAL") (pin "3") (pinfunction "Q0_3") (pintype "unspecified"))
    )
    (net (code "50") (name "/r1D1") (class "Default")
      (node (ref "LED7") (pin "1") (pinfunction "1_1") (pintype "unspecified"))
      (node (ref "REG1") (pin "13") (pinfunction "D4_13") (pintype "unspecified"))
      (node (ref "SOUNDEQUAL") (pin "5") (pinfunction "Q1_5") (pintype "unspecified"))
    )
    (net (code "51") (name "/r1D2") (class "Default")
      (node (ref "LED6") (pin "1") (pinfunction "1_1") (pintype "unspecified"))
      (node (ref "REG1") (pin "14") (pinfunction "D5_14") (pintype "unspecified"))
      (node (ref "SOUNDEQUAL") (pin "7") (pinfunction "Q2_7") (pintype "unspecified"))
    )
    (net (code "52") (name "/r1D3") (class "Default")
      (node (ref "LED5") (pin "1") (pinfunction "1_1") (pintype "unspecified"))
      (node (ref "REG1") (pin "15") (pinfunction "Q5_15") (pintype "unspecified"))
      (node (ref "SOUNDEQUAL") (pin "9") (pinfunction "Q3_9") (pintype "unspecified"))
    )
    (net (code "53") (name "/r1D4") (class "Default")
      (node (ref "LED4") (pin "1") (pinfunction "1_1") (pintype "unspecified"))
      (node (ref "REG1") (pin "16") (pinfunction "Q6_16") (pintype "unspecified"))
      (node (ref "SOUNDEQUAL") (pin "12") (pinfunction "Q4_12") (pintype "unspecified"))
    )
    (net (code "54") (name "/r1D5") (class "Default")
      (node (ref "LED3") (pin "1") (pinfunction "1_1") (pintype "unspecified"))
      (node (ref "REG1") (pin "17") (pinfunction "D6_17") (pintype "unspecified"))
      (node (ref "SOUNDEQUAL") (pin "14") (pinfunction "Q5_14") (pintype "unspecified"))
    )
    (net (code "55") (name "/r1D6") (class "Default")
      (node (ref "LED2") (pin "1") (pinfunction "1_1") (pintype "unspecified"))
      (node (ref "REG1") (pin "18") (pinfunction "D7_18") (pintype "unspecified"))
      (node (ref "SOUNDEQUAL") (pin "16") (pinfunction "Q6_16") (pintype "unspecified"))
    )
    (net (code "56") (name "/r1D7") (class "Default")
      (node (ref "LED1") (pin "1") (pinfunction "1_1") (pintype "unspecified"))
      (node (ref "REG1") (pin "19") (pinfunction "Q7_19") (pintype "unspecified"))
      (node (ref "SOUNDEQUAL") (pin "18") (pinfunction "Q7_18") (pintype "unspecified"))
    )
    (net (code "57") (name "/r2D0") (class "Default")
      (node (ref "REG2") (pin "12") (pinfunction "Q4_12") (pintype "unspecified"))
    )
    (net (code "58") (name "/r2D1") (class "Default")
      (node (ref "REG2") (pin "13") (pinfunction "D4_13") (pintype "unspecified"))
    )
    (net (code "59") (name "/r2D2") (class "Default")
      (node (ref "LED11") (pin "1") (pinfunction "1_1") (pintype "unspecified"))
      (node (ref "REG2") (pin "14") (pinfunction "D5_14") (pintype "unspecified"))
      (node (ref "VR1_1K") (pin "1") (pinfunction "1_1") (pintype "unspecified"))
    )
    (net (code "60") (name "/r2D3") (class "Default")
      (node (ref "LED12") (pin "1") (pinfunction "1_1") (pintype "unspecified"))
      (node (ref "REG2") (pin "15") (pinfunction "Q5_15") (pintype "unspecified"))
      (node (ref "VR3_330") (pin "1") (pinfunction "1_1") (pintype "unspecified"))
    )
    (net (code "61") (name "/r2D4") (class "Default")
      (node (ref "LED13") (pin "1") (pinfunction "1_1") (pintype "unspecified"))
      (node (ref "REG2") (pin "16") (pinfunction "Q6_16") (pintype "unspecified"))
      (node (ref "VR4_150") (pin "1") (pinfunction "1_1") (pintype "unspecified"))
    )
    (net (code "62") (name "/r2D5") (class "Default")
      (node (ref "LED14") (pin "1") (pinfunction "1_1") (pintype "unspecified"))
      (node (ref "REG2") (pin "17") (pinfunction "D6_17") (pintype "unspecified"))
      (node (ref "VR5_68") (pin "1") (pinfunction "1_1") (pintype "unspecified"))
    )
    (net (code "63") (name "/r2D6") (class "Default")
      (node (ref "LED15") (pin "1") (pinfunction "1_1") (pintype "unspecified"))
      (node (ref "REG2") (pin "18") (pinfunction "D7_18") (pintype "unspecified"))
      (node (ref "VR6_30") (pin "1") (pinfunction "1_1") (pintype "unspecified"))
    )
    (net (code "64") (name "/r2D7") (class "Default")
      (node (ref "LED16") (pin "1") (pinfunction "1_1") (pintype "unspecified"))
      (node (ref "REG2") (pin "19") (pinfunction "Q7_19") (pintype "unspecified"))
      (node (ref "VR7_16") (pin "1") (pinfunction "1_1") (pintype "unspecified"))
    )
    (net (code "65") (name "/r3D0") (class "Default")
      (node (ref "LED25") (pin "1") (pinfunction "1_1") (pintype "unspecified"))
      (node (ref "REG3") (pin "12") (pinfunction "Q4_12") (pintype "unspecified"))
      (node (ref "SOUNDEQUAL2") (pin "3") (pinfunction "Q0_3") (pintype "unspecified"))
    )
    (net (code "66") (name "/r3D1") (class "Default")
      (node (ref "LED26") (pin "1") (pinfunction "1_1") (pintype "unspecified"))
      (node (ref "REG3") (pin "13") (pinfunction "D4_13") (pintype "unspecified"))
      (node (ref "SOUNDEQUAL2") (pin "5") (pinfunction "Q1_5") (pintype "unspecified"))
    )
    (net (code "67") (name "/r3D2") (class "Default")
      (node (ref "LED27") (pin "1") (pinfunction "1_1") (pintype "unspecified"))
      (node (ref "REG3") (pin "14") (pinfunction "D5_14") (pintype "unspecified"))
      (node (ref "SOUNDEQUAL2") (pin "7") (pinfunction "Q2_7") (pintype "unspecified"))
    )
    (net (code "68") (name "/r3D3") (class "Default")
      (node (ref "LED28") (pin "1") (pinfunction "1_1") (pintype "unspecified"))
      (node (ref "REG3") (pin "15") (pinfunction "Q5_15") (pintype "unspecified"))
      (node (ref "SOUNDEQUAL2") (pin "9") (pinfunction "Q3_9") (pintype "unspecified"))
    )
    (net (code "69") (name "/r3D4") (class "Default")
      (node (ref "LED29") (pin "1") (pinfunction "1_1") (pintype "unspecified"))
      (node (ref "REG3") (pin "16") (pinfunction "Q6_16") (pintype "unspecified"))
      (node (ref "SOUNDEQUAL2") (pin "12") (pinfunction "Q4_12") (pintype "unspecified"))
    )
    (net (code "70") (name "/r3D5") (class "Default")
      (node (ref "LED30") (pin "1") (pinfunction "1_1") (pintype "unspecified"))
      (node (ref "REG3") (pin "17") (pinfunction "D6_17") (pintype "unspecified"))
      (node (ref "SOUNDEQUAL2") (pin "14") (pinfunction "Q5_14") (pintype "unspecified"))
    )
    (net (code "71") (name "/r3D6") (class "Default")
      (node (ref "LED31") (pin "1") (pinfunction "1_1") (pintype "unspecified"))
      (node (ref "REG3") (pin "18") (pinfunction "D7_18") (pintype "unspecified"))
      (node (ref "SOUNDEQUAL2") (pin "16") (pinfunction "Q6_16") (pintype "unspecified"))
    )
    (net (code "72") (name "/r3D7") (class "Default")
      (node (ref "LED32") (pin "1") (pinfunction "1_1") (pintype "unspecified"))
      (node (ref "REG3") (pin "19") (pinfunction "Q7_19") (pintype "unspecified"))
      (node (ref "SOUNDEQUAL2") (pin "18") (pinfunction "Q7_18") (pintype "unspecified"))
    )
    (net (code "73") (name "/r4D0") (class "Default")
      (node (ref "REG4") (pin "12") (pinfunction "Q4_12") (pintype "unspecified"))
    )
    (net (code "74") (name "/r4D1") (class "Default")
      (node (ref "REG4") (pin "13") (pinfunction "D4_13") (pintype "unspecified"))
    )
    (net (code "75") (name "/r4D2") (class "Default")
      (node (ref "LED22") (pin "1") (pinfunction "1_1") (pintype "unspecified"))
      (node (ref "REG4") (pin "14") (pinfunction "D5_14") (pintype "unspecified"))
      (node (ref "VR14_1K") (pin "1") (pinfunction "1_1") (pintype "unspecified"))
    )
    (net (code "76") (name "/r4D3") (class "Default")
      (node (ref "LED21") (pin "1") (pinfunction "1_1") (pintype "unspecified"))
      (node (ref "REG4") (pin "15") (pinfunction "Q5_15") (pintype "unspecified"))
      (node (ref "VR12_330") (pin "1") (pinfunction "1_1") (pintype "unspecified"))
    )
    (net (code "77") (name "/r4D4") (class "Default")
      (node (ref "LED20") (pin "1") (pinfunction "1_1") (pintype "unspecified"))
      (node (ref "REG4") (pin "16") (pinfunction "Q6_16") (pintype "unspecified"))
      (node (ref "VR11_150") (pin "1") (pinfunction "1_1") (pintype "unspecified"))
    )
    (net (code "78") (name "/r4D5") (class "Default")
      (node (ref "LED19") (pin "1") (pinfunction "1_1") (pintype "unspecified"))
      (node (ref "REG4") (pin "17") (pinfunction "D6_17") (pintype "unspecified"))
      (node (ref "VR10_68") (pin "1") (pinfunction "1_1") (pintype "unspecified"))
    )
    (net (code "79") (name "/r4D6") (class "Default")
      (node (ref "LED18") (pin "1") (pinfunction "1_1") (pintype "unspecified"))
      (node (ref "REG4") (pin "18") (pinfunction "D7_18") (pintype "unspecified"))
      (node (ref "VR9_30") (pin "1") (pinfunction "1_1") (pintype "unspecified"))
    )
    (net (code "80") (name "/r4D7") (class "Default")
      (node (ref "LED17") (pin "1") (pinfunction "1_1") (pintype "unspecified"))
      (node (ref "REG4") (pin "19") (pinfunction "Q7_19") (pintype "unspecified"))
      (node (ref "VR8_16") (pin "1") (pinfunction "1_1") (pintype "unspecified"))
    )
    (net (code "81") (name "/rsE") (class "Default")
      (node (ref "RS") (pin "6") (pinfunction "G2_6") (pintype "unspecified"))
      (node (ref "U1") (pin "11") (pinfunction "4Y_11") (pintype "unspecified"))
    )
    (net (code "82") (name "/r{slash}w") (class "Default")
      (node (ref "DATAPINS") (pin "7") (pinfunction "7_7") (pintype "unspecified"))
      (node (ref "NOR") (pin "8") (pinfunction "A3_8") (pintype "unspecified"))
      (node (ref "NOR") (pin "9") (pinfunction "B3_9") (pintype "unspecified"))
    )
    (net (code "83") (name "/r{slash}wNot") (class "Default")
      (node (ref "NOR") (pin "10") (pinfunction "Y3_10") (pintype "unspecified"))
      (node (ref "U1") (pin "13") (pinfunction "4B_13") (pintype "unspecified"))
    )
    (net (code "84") (name "/s0") (class "Default")
      (node (ref "LOWERSOUNDCOUNTER1") (pin "4") (pinfunction "Q4_4") (pintype "unspecified"))
      (node (ref "SOUNDEQUAL") (pin "2") (pinfunction "P0_2") (pintype "unspecified"))
    )
    (net (code "85") (name "/s1") (class "Default")
      (node (ref "LOWERSOUNDCOUNTER1") (pin "5") (pinfunction "Q5_5") (pintype "unspecified"))
      (node (ref "SOUNDEQUAL") (pin "4") (pinfunction "P1_4") (pintype "unspecified"))
    )
    (net (code "86") (name "/s2") (class "Default")
      (node (ref "LOWERSOUNDCOUNTER1") (pin "6") (pinfunction "Q6_6") (pintype "unspecified"))
      (node (ref "SOUNDEQUAL") (pin "6") (pinfunction "P2_6") (pintype "unspecified"))
    )
    (net (code "87") (name "/s3") (class "Default")
      (node (ref "LOWERSOUNDCOUNTER1") (pin "7") (pinfunction "Q7_7") (pintype "unspecified"))
      (node (ref "SOUNDEQUAL") (pin "8") (pinfunction "P3_8") (pintype "unspecified"))
    )
    (net (code "88") (name "/s4") (class "Default")
      (node (ref "SOUNDEQUAL") (pin "11") (pinfunction "P4_11") (pintype "unspecified"))
      (node (ref "UPPERSOUNDCOUNTER1") (pin "15") (pinfunction "Q0_15") (pintype "unspecified"))
    )
    (net (code "89") (name "/s5") (class "Default")
      (node (ref "SOUNDEQUAL") (pin "13") (pinfunction "P5_13") (pintype "unspecified"))
      (node (ref "UPPERSOUNDCOUNTER1") (pin "1") (pinfunction "Q1_1") (pintype "unspecified"))
    )
    (net (code "90") (name "/s6") (class "Default")
      (node (ref "SOUNDEQUAL") (pin "15") (pinfunction "P6_15") (pintype "unspecified"))
      (node (ref "UPPERSOUNDCOUNTER1") (pin "2") (pinfunction "Q2_2") (pintype "unspecified"))
    )
    (net (code "91") (name "/s7") (class "Default")
      (node (ref "SOUNDEQUAL") (pin "17") (pinfunction "P7_17") (pintype "unspecified"))
      (node (ref "UPPERSOUNDCOUNTER1") (pin "3") (pinfunction "Q3_3") (pintype "unspecified"))
    )
    (net (code "92") (name "/s10") (class "Default")
      (node (ref "LOWERSOUNDCOUNTER2") (pin "4") (pinfunction "Q4_4") (pintype "unspecified"))
      (node (ref "SOUNDEQUAL2") (pin "2") (pinfunction "P0_2") (pintype "unspecified"))
    )
    (net (code "93") (name "/s11") (class "Default")
      (node (ref "LOWERSOUNDCOUNTER2") (pin "5") (pinfunction "Q5_5") (pintype "unspecified"))
      (node (ref "SOUNDEQUAL2") (pin "4") (pinfunction "P1_4") (pintype "unspecified"))
    )
    (net (code "94") (name "/s12") (class "Default")
      (node (ref "LOWERSOUNDCOUNTER2") (pin "6") (pinfunction "Q6_6") (pintype "unspecified"))
      (node (ref "SOUNDEQUAL2") (pin "6") (pinfunction "P2_6") (pintype "unspecified"))
    )
    (net (code "95") (name "/s13") (class "Default")
      (node (ref "LOWERSOUNDCOUNTER2") (pin "7") (pinfunction "Q7_7") (pintype "unspecified"))
      (node (ref "SOUNDEQUAL2") (pin "8") (pinfunction "P3_8") (pintype "unspecified"))
    )
    (net (code "96") (name "/s14") (class "Default")
      (node (ref "SOUNDEQUAL2") (pin "11") (pinfunction "P4_11") (pintype "unspecified"))
      (node (ref "UPPERSOUNDCOUNTER2") (pin "15") (pinfunction "Q0_15") (pintype "unspecified"))
    )
    (net (code "97") (name "/s15") (class "Default")
      (node (ref "SOUNDEQUAL2") (pin "13") (pinfunction "P5_13") (pintype "unspecified"))
      (node (ref "UPPERSOUNDCOUNTER2") (pin "1") (pinfunction "Q1_1") (pintype "unspecified"))
    )
    (net (code "98") (name "/s16") (class "Default")
      (node (ref "SOUNDEQUAL2") (pin "15") (pinfunction "P6_15") (pintype "unspecified"))
      (node (ref "UPPERSOUNDCOUNTER2") (pin "2") (pinfunction "Q2_2") (pintype "unspecified"))
    )
    (net (code "99") (name "/s17") (class "Default")
      (node (ref "SOUNDEQUAL2") (pin "17") (pinfunction "P7_17") (pintype "unspecified"))
      (node (ref "UPPERSOUNDCOUNTER2") (pin "3") (pinfunction "Q3_3") (pintype "unspecified"))
    )
    (net (code "100") (name "/soundOutput1") (class "Default")
      (node (ref "REG2") (pin "1") (pinfunction "E#_1") (pintype "unspecified"))
      (node (ref "SOUNDOUTPUTCOUNTER1") (pin "15") (pinfunction "Q0_15") (pintype "unspecified"))
      (node (ref "SPEAKER1OUTPUT") (pin "1") (pinfunction "1_1") (pintype "input"))
    )
    (net (code "101") (name "/soundOutput2") (class "Default")
      (node (ref "REG4") (pin "1") (pinfunction "E#_1") (pintype "unspecified"))
      (node (ref "SOUNDOUTPUTCOUNTER2") (pin "15") (pinfunction "Q0_15") (pintype "unspecified"))
      (node (ref "SPEAKER2OUTPUT") (pin "1") (pinfunction "1_1") (pintype "input"))
    )
    (net (code "102") (name "/store1") (class "Default")
      (node (ref "REG1") (pin "11") (pinfunction "CP_11") (pintype "unspecified"))
      (node (ref "RS") (pin "15") (pinfunction "Y0_15") (pintype "unspecified"))
    )
    (net (code "103") (name "/store2") (class "Default")
      (node (ref "REG2") (pin "11") (pinfunction "CP_11") (pintype "unspecified"))
      (node (ref "RS") (pin "14") (pinfunction "Y1_14") (pintype "unspecified"))
    )
    (net (code "104") (name "/store3") (class "Default")
      (node (ref "REG3") (pin "11") (pinfunction "CP_11") (pintype "unspecified"))
      (node (ref "RS") (pin "13") (pinfunction "Y2_13") (pintype "unspecified"))
    )
    (net (code "105") (name "/store4") (class "Default")
      (node (ref "REG4") (pin "11") (pinfunction "CP_11") (pintype "unspecified"))
      (node (ref "RS") (pin "12") (pinfunction "Y3_12") (pintype "unspecified"))
    )
    (net (code "106") (name "/store5") (class "Default")
      (node (ref "RS") (pin "11") (pinfunction "Y4_11") (pintype "unspecified"))
    )
    (net (code "107") (name "/store6") (class "Default")
      (node (ref "RS") (pin "10") (pinfunction "Y5_10") (pintype "unspecified"))
    )
    (net (code "108") (name "/store7") (class "Default")
      (node (ref "RS") (pin "9") (pinfunction "Y6_9") (pintype "unspecified"))
    )
    (net (code "109") (name "/store8") (class "Default")
      (node (ref "RS") (pin "7") (pinfunction "Y7_7") (pintype "unspecified"))
    )
    (net (code "110") (name "/totalSoundOutput") (class "Default")
      (node (ref "BUZZER1") (pin "2") (pinfunction "+_2") (pintype "unspecified"))
      (node (ref "COMBINEDOUTPUT") (pin "1") (pinfunction "1_1") (pintype "input"))
      (node (ref "VR10_68") (pin "2") (pinfunction "2_2") (pintype "unspecified"))
      (node (ref "VR11_150") (pin "2") (pinfunction "2_2") (pintype "unspecified"))
      (node (ref "VR12_330") (pin "2") (pinfunction "2_2") (pintype "unspecified"))
      (node (ref "VR13_1K") (pin "1") (pinfunction "1_1") (pintype "unspecified"))
      (node (ref "VR14_1K") (pin "2") (pinfunction "2_2") (pintype "unspecified"))
      (node (ref "VR1_1K") (pin "2") (pinfunction "2_2") (pintype "unspecified"))
      (node (ref "VR2_1K") (pin "1") (pinfunction "1_1") (pintype "unspecified"))
      (node (ref "VR3_330") (pin "2") (pinfunction "2_2") (pintype "unspecified"))
      (node (ref "VR4_150") (pin "2") (pinfunction "2_2") (pintype "unspecified"))
      (node (ref "VR5_68") (pin "2") (pinfunction "2_2") (pintype "unspecified"))
      (node (ref "VR6_30") (pin "2") (pinfunction "2_2") (pintype "unspecified"))
      (node (ref "VR7_16") (pin "2") (pinfunction "2_2") (pintype "unspecified"))
      (node (ref "VR8_16") (pin "2") (pinfunction "2_2") (pintype "unspecified"))
      (node (ref "VR9_30") (pin "2") (pinfunction "2_2") (pintype "unspecified"))
    )
    (net (code "111") (name "GND") (class "Default")
      (node (ref "ADDRESSCHECKER1") (pin "10") (pinfunction "GND_10") (pintype "unspecified"))
      (node (ref "ADDRESSCHECKER2") (pin "10") (pinfunction "GND_10") (pintype "unspecified"))
      (node (ref "ADDRESSCHECKER2") (pin "2") (pinfunction "P0_2") (pintype "unspecified"))
      (node (ref "ADDRESSCHECKER2") (pin "3") (pinfunction "Q0_3") (pintype "unspecified"))
      (node (ref "ADDRESSCHECKER2") (pin "4") (pinfunction "P1_4") (pintype "unspecified"))
      (node (ref "ADDRESSCHECKER2") (pin "5") (pinfunction "Q1_5") (pintype "unspecified"))
      (node (ref "ADDRESSCHECKER2") (pin "6") (pinfunction "P2_6") (pintype "unspecified"))
      (node (ref "ADDRESSCHECKER2") (pin "7") (pinfunction "Q2_7") (pintype "unspecified"))
      (node (ref "COMBINEDOUTPUT") (pin "2") (pinfunction "2_2") (pintype "input"))
      (node (ref "DATAPINS") (pin "1") (pinfunction "1_1") (pintype "unspecified"))
      (node (ref "LOWERSOUNDCOUNTER1") (pin "8") (pinfunction "GND_8") (pintype "unspecified"))
      (node (ref "LOWERSOUNDCOUNTER2") (pin "8") (pinfunction "GND_8") (pintype "unspecified"))
      (node (ref "NOR") (pin "7") (pinfunction "GND_7") (pintype "unspecified"))
      (node (ref "R1") (pin "1") (pinfunction "1_1") (pintype "unspecified"))
      (node (ref "R10") (pin "2") (pinfunction "2_2") (pintype "unspecified"))
      (node (ref "R11") (pin "2") (pinfunction "2_2") (pintype "unspecified"))
      (node (ref "R12") (pin "2") (pinfunction "2_2") (pintype "unspecified"))
      (node (ref "R13") (pin "2") (pinfunction "2_2") (pintype "unspecified"))
      (node (ref "R14") (pin "2") (pinfunction "2_2") (pintype "unspecified"))
      (node (ref "R15") (pin "2") (pinfunction "2_2") (pintype "unspecified"))
      (node (ref "R16") (pin "2") (pinfunction "2_2") (pintype "unspecified"))
      (node (ref "R17") (pin "2") (pinfunction "2_2") (pintype "unspecified"))
      (node (ref "R18") (pin "2") (pinfunction "2_2") (pintype "unspecified"))
      (node (ref "R19") (pin "2") (pinfunction "2_2") (pintype "unspecified"))
      (node (ref "R2") (pin "1") (pinfunction "1_1") (pintype "unspecified"))
      (node (ref "R20") (pin "2") (pinfunction "2_2") (pintype "unspecified"))
      (node (ref "R21") (pin "2") (pinfunction "2_2") (pintype "unspecified"))
      (node (ref "R22") (pin "2") (pinfunction "2_2") (pintype "unspecified"))
      (node (ref "R23") (pin "2") (pinfunction "2_2") (pintype "unspecified"))
      (node (ref "R24") (pin "2") (pinfunction "2_2") (pintype "unspecified"))
      (node (ref "R25") (pin "2") (pinfunction "2_2") (pintype "unspecified"))
      (node (ref "R26") (pin "2") (pinfunction "2_2") (pintype "unspecified"))
      (node (ref "R27") (pin "2") (pinfunction "2_2") (pintype "unspecified"))
      (node (ref "R28") (pin "2") (pinfunction "2_2") (pintype "unspecified"))
      (node (ref "R29") (pin "2") (pinfunction "2_2") (pintype "unspecified"))
      (node (ref "R3") (pin "1") (pinfunction "1_1") (pintype "unspecified"))
      (node (ref "R30") (pin "2") (pinfunction "2_2") (pintype "unspecified"))
      (node (ref "R31") (pin "2") (pinfunction "2_2") (pintype "unspecified"))
      (node (ref "R32") (pin "2") (pinfunction "2_2") (pintype "unspecified"))
      (node (ref "R33") (pin "2") (pinfunction "2_2") (pintype "unspecified"))
      (node (ref "R34") (pin "2") (pinfunction "2_2") (pintype "unspecified"))
      (node (ref "R37") (pin "2") (pinfunction "2_2") (pintype "unspecified"))
      (node (ref "R38") (pin "2") (pinfunction "2_2") (pintype "unspecified"))
      (node (ref "R39") (pin "2") (pinfunction "2_2") (pintype "unspecified"))
      (node (ref "R4") (pin "2") (pinfunction "2_2") (pintype "unspecified"))
      (node (ref "R40") (pin "2") (pinfunction "2_2") (pintype "unspecified"))
      (node (ref "R41") (pin "2") (pinfunction "2_2") (pintype "unspecified"))
      (node (ref "R42") (pin "2") (pinfunction "2_2") (pintype "unspecified"))
      (node (ref "R45") (pin "2") (pinfunction "2_2") (pintype "unspecified"))
      (node (ref "R46") (pin "2") (pinfunction "2_2") (pintype "unspecified"))
      (node (ref "R47") (pin "2") (pinfunction "2_2") (pintype "unspecified"))
      (node (ref "R48") (pin "2") (pinfunction "2_2") (pintype "unspecified"))
      (node (ref "R49") (pin "2") (pinfunction "2_2") (pintype "unspecified"))
      (node (ref "R5") (pin "2") (pinfunction "2_2") (pintype "unspecified"))
      (node (ref "R50") (pin "2") (pinfunction "2_2") (pintype "unspecified"))
      (node (ref "R53") (pin "2") (pinfunction "2_2") (pintype "unspecified"))
      (node (ref "R54") (pin "2") (pinfunction "2_2") (pintype "unspecified"))
      (node (ref "R55") (pin "2") (pinfunction "2_2") (pintype "unspecified"))
      (node (ref "R56") (pin "2") (pinfunction "2_2") (pintype "unspecified"))
      (node (ref "R57") (pin "2") (pinfunction "2_2") (pintype "unspecified"))
      (node (ref "R58") (pin "2") (pinfunction "2_2") (pintype "unspecified"))
      (node (ref "R59") (pin "2") (pinfunction "2_2") (pintype "unspecified"))
      (node (ref "R6") (pin "1") (pinfunction "1_1") (pintype "unspecified"))
      (node (ref "R60") (pin "2") (pinfunction "2_2") (pintype "unspecified"))
      (node (ref "R61") (pin "1") (pinfunction "1_1") (pintype "unspecified"))
      (node (ref "R63") (pin "2") (pinfunction "2_2") (pintype "unspecified"))
      (node (ref "R64") (pin "2") (pinfunction "2_2") (pintype "unspecified"))
      (node (ref "R65") (pin "1") (pinfunction "1_1") (pintype "unspecified"))
      (node (ref "R66") (pin "2") (pinfunction "2_2") (pintype "unspecified"))
      (node (ref "R67") (pin "2") (pinfunction "2_2") (pintype "unspecified"))
      (node (ref "R7") (pin "2") (pinfunction "2_2") (pintype "unspecified"))
      (node (ref "R8") (pin "2") (pinfunction "2_2") (pintype "unspecified"))
      (node (ref "REG1") (pin "10") (pinfunction "GND_10") (pintype "unspecified"))
      (node (ref "REG2") (pin "10") (pinfunction "GND_10") (pintype "unspecified"))
      (node (ref "REG3") (pin "10") (pinfunction "GND_10") (pintype "unspecified"))
      (node (ref "REG4") (pin "10") (pinfunction "GND_10") (pintype "unspecified"))
      (node (ref "RS") (pin "8") (pinfunction "GND_8") (pintype "unspecified"))
      (node (ref "SOUNDEQUAL") (pin "10") (pinfunction "GND_10") (pintype "unspecified"))
      (node (ref "SOUNDEQUAL2") (pin "10") (pinfunction "GND_10") (pintype "unspecified"))
      (node (ref "SOUNDOUTPUTCOUNTER1") (pin "8") (pinfunction "GND_8") (pintype "unspecified"))
      (node (ref "SOUNDOUTPUTCOUNTER2") (pin "8") (pinfunction "GND_8") (pintype "unspecified"))
      (node (ref "SPEAKER1OUTPUT") (pin "2") (pinfunction "2_2") (pintype "input"))
      (node (ref "SPEAKER2OUTPUT") (pin "2") (pinfunction "2_2") (pintype "input"))
      (node (ref "U1") (pin "7") (pinfunction "GND_7") (pintype "unspecified"))
      (node (ref "UPPERSOUNDCOUNTER1") (pin "8") (pinfunction "GND_8") (pintype "unspecified"))
      (node (ref "UPPERSOUNDCOUNTER2") (pin "8") (pinfunction "GND_8") (pintype "unspecified"))
      (node (ref "VR13_1K") (pin "2") (pinfunction "2_2") (pintype "unspecified"))
      (node (ref "VR2_1K") (pin "2") (pinfunction "2_2") (pintype "unspecified"))
    )
    (net (code "112") (name "Net-(ADDRESSCHECKER1-OE#)") (class "Default")
      (node (ref "ADDRESSCHECKER1") (pin "1") (pinfunction "OE#_1") (pintype "unspecified"))
      (node (ref "R1") (pin "2") (pinfunction "2_2") (pintype "unspecified"))
    )
    (net (code "113") (name "Net-(ADDRESSCHECKER2-OE#)") (class "Default")
      (node (ref "ADDRESSCHECKER2") (pin "1") (pinfunction "OE#_1") (pintype "unspecified"))
      (node (ref "R2") (pin "2") (pinfunction "2_2") (pintype "unspecified"))
    )
    (net (code "114") (name "Net-(BUZZER1--)") (class "Default")
      (node (ref "BUZZER1") (pin "1") (pinfunction "-_1") (pintype "unspecified"))
      (node (ref "R12") (pin "3") (pinfunction "3_3") (pintype "unspecified"))
    )
    (net (code "115") (name "Net-(LED1-Pad2)") (class "Default")
      (node (ref "LED1") (pin "2") (pinfunction "2_2") (pintype "unspecified"))
      (node (ref "R11") (pin "1") (pinfunction "1_1") (pintype "unspecified"))
    )
    (net (code "116") (name "Net-(LED2-Pad2)") (class "Default")
      (node (ref "LED2") (pin "2") (pinfunction "2_2") (pintype "unspecified"))
      (node (ref "R22") (pin "1") (pinfunction "1_1") (pintype "unspecified"))
    )
    (net (code "117") (name "Net-(LED3-Pad2)") (class "Default")
      (node (ref "LED3") (pin "2") (pinfunction "2_2") (pintype "unspecified"))
      (node (ref "R29") (pin "1") (pinfunction "1_1") (pintype "unspecified"))
    )
    (net (code "118") (name "Net-(LED4-Pad2)") (class "Default")
      (node (ref "LED4") (pin "2") (pinfunction "2_2") (pintype "unspecified"))
      (node (ref "R30") (pin "1") (pinfunction "1_1") (pintype "unspecified"))
    )
    (net (code "119") (name "Net-(LED5-Pad2)") (class "Default")
      (node (ref "LED5") (pin "2") (pinfunction "2_2") (pintype "unspecified"))
      (node (ref "R31") (pin "1") (pinfunction "1_1") (pintype "unspecified"))
    )
    (net (code "120") (name "Net-(LED6-Pad2)") (class "Default")
      (node (ref "LED6") (pin "2") (pinfunction "2_2") (pintype "unspecified"))
      (node (ref "R32") (pin "1") (pinfunction "1_1") (pintype "unspecified"))
    )
    (net (code "121") (name "Net-(LED7-Pad2)") (class "Default")
      (node (ref "LED7") (pin "2") (pinfunction "2_2") (pintype "unspecified"))
      (node (ref "R33") (pin "1") (pinfunction "1_1") (pintype "unspecified"))
    )
    (net (code "122") (name "Net-(LED8-Pad2)") (class "Default")
      (node (ref "LED8") (pin "2") (pinfunction "2_2") (pintype "unspecified"))
      (node (ref "R34") (pin "1") (pinfunction "1_1") (pintype "unspecified"))
    )
    (net (code "123") (name "Net-(LED11-Pad2)") (class "Default")
      (node (ref "LED11") (pin "2") (pinfunction "2_2") (pintype "unspecified"))
      (node (ref "R37") (pin "1") (pinfunction "1_1") (pintype "unspecified"))
    )
    (net (code "124") (name "Net-(LED12-Pad2)") (class "Default")
      (node (ref "LED12") (pin "2") (pinfunction "2_2") (pintype "unspecified"))
      (node (ref "R38") (pin "1") (pinfunction "1_1") (pintype "unspecified"))
    )
    (net (code "125") (name "Net-(LED13-Pad2)") (class "Default")
      (node (ref "LED13") (pin "2") (pinfunction "2_2") (pintype "unspecified"))
      (node (ref "R39") (pin "1") (pinfunction "1_1") (pintype "unspecified"))
    )
    (net (code "126") (name "Net-(LED14-Pad2)") (class "Default")
      (node (ref "LED14") (pin "2") (pinfunction "2_2") (pintype "unspecified"))
      (node (ref "R40") (pin "1") (pinfunction "1_1") (pintype "unspecified"))
    )
    (net (code "127") (name "Net-(LED15-Pad2)") (class "Default")
      (node (ref "LED15") (pin "2") (pinfunction "2_2") (pintype "unspecified"))
      (node (ref "R41") (pin "1") (pinfunction "1_1") (pintype "unspecified"))
    )
    (net (code "128") (name "Net-(LED16-Pad2)") (class "Default")
      (node (ref "LED16") (pin "2") (pinfunction "2_2") (pintype "unspecified"))
      (node (ref "R42") (pin "1") (pinfunction "1_1") (pintype "unspecified"))
    )
    (net (code "129") (name "Net-(LED17-Pad2)") (class "Default")
      (node (ref "LED17") (pin "2") (pinfunction "2_2") (pintype "unspecified"))
      (node (ref "R45") (pin "1") (pinfunction "1_1") (pintype "unspecified"))
    )
    (net (code "130") (name "Net-(LED18-Pad2)") (class "Default")
      (node (ref "LED18") (pin "2") (pinfunction "2_2") (pintype "unspecified"))
      (node (ref "R46") (pin "1") (pinfunction "1_1") (pintype "unspecified"))
    )
    (net (code "131") (name "Net-(LED19-Pad2)") (class "Default")
      (node (ref "LED19") (pin "2") (pinfunction "2_2") (pintype "unspecified"))
      (node (ref "R47") (pin "1") (pinfunction "1_1") (pintype "unspecified"))
    )
    (net (code "132") (name "Net-(LED20-Pad2)") (class "Default")
      (node (ref "LED20") (pin "2") (pinfunction "2_2") (pintype "unspecified"))
      (node (ref "R48") (pin "1") (pinfunction "1_1") (pintype "unspecified"))
    )
    (net (code "133") (name "Net-(LED21-Pad2)") (class "Default")
      (node (ref "LED21") (pin "2") (pinfunction "2_2") (pintype "unspecified"))
      (node (ref "R49") (pin "1") (pinfunction "1_1") (pintype "unspecified"))
    )
    (net (code "134") (name "Net-(LED22-Pad2)") (class "Default")
      (node (ref "LED22") (pin "2") (pinfunction "2_2") (pintype "unspecified"))
      (node (ref "R50") (pin "1") (pinfunction "1_1") (pintype "unspecified"))
    )
    (net (code "135") (name "Net-(LED25-Pad2)") (class "Default")
      (node (ref "LED25") (pin "2") (pinfunction "2_2") (pintype "unspecified"))
      (node (ref "R53") (pin "1") (pinfunction "1_1") (pintype "unspecified"))
    )
    (net (code "136") (name "Net-(LED26-Pad2)") (class "Default")
      (node (ref "LED26") (pin "2") (pinfunction "2_2") (pintype "unspecified"))
      (node (ref "R54") (pin "1") (pinfunction "1_1") (pintype "unspecified"))
    )
    (net (code "137") (name "Net-(LED27-Pad2)") (class "Default")
      (node (ref "LED27") (pin "2") (pinfunction "2_2") (pintype "unspecified"))
      (node (ref "R55") (pin "1") (pinfunction "1_1") (pintype "unspecified"))
    )
    (net (code "138") (name "Net-(LED28-Pad2)") (class "Default")
      (node (ref "LED28") (pin "2") (pinfunction "2_2") (pintype "unspecified"))
      (node (ref "R56") (pin "1") (pinfunction "1_1") (pintype "unspecified"))
    )
    (net (code "139") (name "Net-(LED29-Pad2)") (class "Default")
      (node (ref "LED29") (pin "2") (pinfunction "2_2") (pintype "unspecified"))
      (node (ref "R57") (pin "1") (pinfunction "1_1") (pintype "unspecified"))
    )
    (net (code "140") (name "Net-(LED30-Pad2)") (class "Default")
      (node (ref "LED30") (pin "2") (pinfunction "2_2") (pintype "unspecified"))
      (node (ref "R58") (pin "1") (pinfunction "1_1") (pintype "unspecified"))
    )
    (net (code "141") (name "Net-(LED31-Pad2)") (class "Default")
      (node (ref "LED31") (pin "2") (pinfunction "2_2") (pintype "unspecified"))
      (node (ref "R59") (pin "1") (pinfunction "1_1") (pintype "unspecified"))
    )
    (net (code "142") (name "Net-(LED32-Pad2)") (class "Default")
      (node (ref "LED32") (pin "2") (pinfunction "2_2") (pintype "unspecified"))
      (node (ref "R60") (pin "1") (pinfunction "1_1") (pintype "unspecified"))
    )
    (net (code "143") (name "Net-(LOWERSOUNDCOUNTER1-CE#)") (class "Default")
      (node (ref "LOWERSOUNDCOUNTER1") (pin "10") (pinfunction "MRC#_10") (pintype "unspecified"))
      (node (ref "LOWERSOUNDCOUNTER1") (pin "12") (pinfunction "CE#_12") (pintype "unspecified"))
      (node (ref "R4") (pin "1") (pinfunction "1_1") (pintype "unspecified"))
      (node (ref "UPPERSOUNDCOUNTER1") (pin "10") (pinfunction "MRC#_10") (pintype "unspecified"))
      (node (ref "UPPERSOUNDCOUNTER1") (pin "12") (pinfunction "CE#_12") (pintype "unspecified"))
    )
    (net (code "144") (name "Net-(LOWERSOUNDCOUNTER1-RCO#)") (class "Default")
      (node (ref "LOWERSOUNDCOUNTER1") (pin "9") (pinfunction "RCO#_9") (pintype "unspecified"))
      (node (ref "UPPERSOUNDCOUNTER1") (pin "11") (pinfunction "CPC_11") (pintype "unspecified"))
      (node (ref "UPPERSOUNDCOUNTER1") (pin "13") (pinfunction "CPR_13") (pintype "unspecified"))
    )
    (net (code "145") (name "Net-(LOWERSOUNDCOUNTER2-CE#)") (class "Default")
      (node (ref "LOWERSOUNDCOUNTER2") (pin "10") (pinfunction "MRC#_10") (pintype "unspecified"))
      (node (ref "LOWERSOUNDCOUNTER2") (pin "12") (pinfunction "CE#_12") (pintype "unspecified"))
      (node (ref "R67") (pin "1") (pinfunction "1_1") (pintype "unspecified"))
      (node (ref "UPPERSOUNDCOUNTER2") (pin "10") (pinfunction "MRC#_10") (pintype "unspecified"))
      (node (ref "UPPERSOUNDCOUNTER2") (pin "12") (pinfunction "CE#_12") (pintype "unspecified"))
    )
    (net (code "146") (name "Net-(LOWERSOUNDCOUNTER2-RCO#)") (class "Default")
      (node (ref "LOWERSOUNDCOUNTER2") (pin "9") (pinfunction "RCO#_9") (pintype "unspecified"))
      (node (ref "UPPERSOUNDCOUNTER2") (pin "11") (pinfunction "CPC_11") (pintype "unspecified"))
      (node (ref "UPPERSOUNDCOUNTER2") (pin "13") (pinfunction "CPR_13") (pintype "unspecified"))
    )
    (net (code "147") (name "Net-(REG1-E#)") (class "Default")
      (node (ref "R3") (pin "2") (pinfunction "2_2") (pintype "unspecified"))
      (node (ref "REG1") (pin "1") (pinfunction "E#_1") (pintype "unspecified"))
    )
    (net (code "148") (name "Net-(REG3-E#)") (class "Default")
      (node (ref "R61") (pin "2") (pinfunction "2_2") (pintype "unspecified"))
      (node (ref "REG3") (pin "1") (pinfunction "E#_1") (pintype "unspecified"))
    )
    (net (code "149") (name "Net-(SOUNDEQUAL-#P=Q)") (class "Default")
      (node (ref "SOUNDEQUAL") (pin "19") (pinfunction "#P=Q_19") (pintype "unspecified"))
      (node (ref "SOUNDOUTPUTCOUNTER1") (pin "11") (pinfunction "CPC_11") (pintype "unspecified"))
      (node (ref "SOUNDOUTPUTCOUNTER1") (pin "13") (pinfunction "CPR_13") (pintype "unspecified"))
    )
    (net (code "150") (name "Net-(SOUNDEQUAL-OE#)") (class "Default")
      (node (ref "R6") (pin "2") (pinfunction "2_2") (pintype "unspecified"))
      (node (ref "SOUNDEQUAL") (pin "1") (pinfunction "OE#_1") (pintype "unspecified"))
    )
    (net (code "151") (name "Net-(SOUNDEQUAL2-#P=Q)") (class "Default")
      (node (ref "SOUNDEQUAL2") (pin "19") (pinfunction "#P=Q_19") (pintype "unspecified"))
      (node (ref "SOUNDOUTPUTCOUNTER2") (pin "11") (pinfunction "CPC_11") (pintype "unspecified"))
      (node (ref "SOUNDOUTPUTCOUNTER2") (pin "13") (pinfunction "CPR_13") (pintype "unspecified"))
    )
    (net (code "152") (name "Net-(SOUNDEQUAL2-OE#)") (class "Default")
      (node (ref "R65") (pin "2") (pinfunction "2_2") (pintype "unspecified"))
      (node (ref "SOUNDEQUAL2") (pin "1") (pinfunction "OE#_1") (pintype "unspecified"))
    )
    (net (code "153") (name "Net-(SOUNDOUTPUTCOUNTER1-CE#)") (class "Default")
      (node (ref "R8") (pin "1") (pinfunction "1_1") (pintype "unspecified"))
      (node (ref "SOUNDOUTPUTCOUNTER1") (pin "12") (pinfunction "CE#_12") (pintype "unspecified"))
    )
    (net (code "154") (name "Net-(SOUNDOUTPUTCOUNTER1-MRC#)") (class "Default")
      (node (ref "R9") (pin "1") (pinfunction "1_1") (pintype "unspecified"))
      (node (ref "SOUNDOUTPUTCOUNTER1") (pin "10") (pinfunction "MRC#_10") (pintype "unspecified"))
    )
    (net (code "155") (name "Net-(SOUNDOUTPUTCOUNTER1-OE#)") (class "Default")
      (node (ref "R7") (pin "1") (pinfunction "1_1") (pintype "unspecified"))
      (node (ref "SOUNDOUTPUTCOUNTER1") (pin "14") (pinfunction "OE#_14") (pintype "unspecified"))
    )
    (net (code "156") (name "Net-(SOUNDOUTPUTCOUNTER2-CE#)") (class "Default")
      (node (ref "R63") (pin "1") (pinfunction "1_1") (pintype "unspecified"))
      (node (ref "SOUNDOUTPUTCOUNTER2") (pin "12") (pinfunction "CE#_12") (pintype "unspecified"))
    )
    (net (code "157") (name "Net-(SOUNDOUTPUTCOUNTER2-MRC#)") (class "Default")
      (node (ref "R62") (pin "1") (pinfunction "1_1") (pintype "unspecified"))
      (node (ref "SOUNDOUTPUTCOUNTER2") (pin "10") (pinfunction "MRC#_10") (pintype "unspecified"))
    )
    (net (code "158") (name "Net-(SOUNDOUTPUTCOUNTER2-OE#)") (class "Default")
      (node (ref "R64") (pin "1") (pinfunction "1_1") (pintype "unspecified"))
      (node (ref "SOUNDOUTPUTCOUNTER2") (pin "14") (pinfunction "OE#_14") (pintype "unspecified"))
    )
    (net (code "159") (name "Net-(UPPERSOUNDCOUNTER1-OE#)") (class "Default")
      (node (ref "R5") (pin "1") (pinfunction "1_1") (pintype "unspecified"))
      (node (ref "UPPERSOUNDCOUNTER1") (pin "14") (pinfunction "OE#_14") (pintype "unspecified"))
    )
    (net (code "160") (name "Net-(UPPERSOUNDCOUNTER2-OE#)") (class "Default")
      (node (ref "R66") (pin "1") (pinfunction "1_1") (pintype "unspecified"))
      (node (ref "UPPERSOUNDCOUNTER2") (pin "14") (pinfunction "OE#_14") (pintype "unspecified"))
    )
    (net (code "161") (name "unconnected-(LOWERSOUNDCOUNTER1-OE#-Pad14)") (class "Default")
      (node (ref "LOWERSOUNDCOUNTER1") (pin "14") (pinfunction "OE#_14") (pintype "unspecified"))
    )
    (net (code "162") (name "unconnected-(LOWERSOUNDCOUNTER1-Q0-Pad15)") (class "Default")
      (node (ref "LOWERSOUNDCOUNTER1") (pin "15") (pinfunction "Q0_15") (pintype "unspecified"))
    )
    (net (code "163") (name "unconnected-(LOWERSOUNDCOUNTER1-Q1-Pad1)") (class "Default")
      (node (ref "LOWERSOUNDCOUNTER1") (pin "1") (pinfunction "Q1_1") (pintype "unspecified"))
    )
    (net (code "164") (name "unconnected-(LOWERSOUNDCOUNTER1-Q2-Pad2)") (class "Default")
      (node (ref "LOWERSOUNDCOUNTER1") (pin "2") (pinfunction "Q2_2") (pintype "unspecified"))
    )
    (net (code "165") (name "unconnected-(LOWERSOUNDCOUNTER1-Q3-Pad3)") (class "Default")
      (node (ref "LOWERSOUNDCOUNTER1") (pin "3") (pinfunction "Q3_3") (pintype "unspecified"))
    )
    (net (code "166") (name "unconnected-(LOWERSOUNDCOUNTER2-OE#-Pad14)") (class "Default")
      (node (ref "LOWERSOUNDCOUNTER2") (pin "14") (pinfunction "OE#_14") (pintype "unspecified"))
    )
    (net (code "167") (name "unconnected-(LOWERSOUNDCOUNTER2-Q0-Pad15)") (class "Default")
      (node (ref "LOWERSOUNDCOUNTER2") (pin "15") (pinfunction "Q0_15") (pintype "unspecified"))
    )
    (net (code "168") (name "unconnected-(LOWERSOUNDCOUNTER2-Q1-Pad1)") (class "Default")
      (node (ref "LOWERSOUNDCOUNTER2") (pin "1") (pinfunction "Q1_1") (pintype "unspecified"))
    )
    (net (code "169") (name "unconnected-(LOWERSOUNDCOUNTER2-Q2-Pad2)") (class "Default")
      (node (ref "LOWERSOUNDCOUNTER2") (pin "2") (pinfunction "Q2_2") (pintype "unspecified"))
    )
    (net (code "170") (name "unconnected-(LOWERSOUNDCOUNTER2-Q3-Pad3)") (class "Default")
      (node (ref "LOWERSOUNDCOUNTER2") (pin "3") (pinfunction "Q3_3") (pintype "unspecified"))
    )
    (net (code "171") (name "unconnected-(NOR-A1-Pad2)") (class "Default")
      (node (ref "NOR") (pin "2") (pinfunction "A1_2") (pintype "unspecified"))
    )
    (net (code "172") (name "unconnected-(NOR-A2-Pad5)") (class "Default")
      (node (ref "NOR") (pin "5") (pinfunction "A2_5") (pintype "unspecified"))
    )
    (net (code "173") (name "unconnected-(NOR-A4-Pad11)") (class "Default")
      (node (ref "NOR") (pin "11") (pinfunction "A4_11") (pintype "unspecified"))
    )
    (net (code "174") (name "unconnected-(NOR-B1-Pad3)") (class "Default")
      (node (ref "NOR") (pin "3") (pinfunction "B1_3") (pintype "unspecified"))
    )
    (net (code "175") (name "unconnected-(NOR-B2-Pad6)") (class "Default")
      (node (ref "NOR") (pin "6") (pinfunction "B2_6") (pintype "unspecified"))
    )
    (net (code "176") (name "unconnected-(NOR-B4-Pad12)") (class "Default")
      (node (ref "NOR") (pin "12") (pinfunction "B4_12") (pintype "unspecified"))
    )
    (net (code "177") (name "unconnected-(NOR-Y1-Pad1)") (class "Default")
      (node (ref "NOR") (pin "1") (pinfunction "Y1_1") (pintype "unspecified"))
    )
    (net (code "178") (name "unconnected-(NOR-Y2-Pad4)") (class "Default")
      (node (ref "NOR") (pin "4") (pinfunction "Y2_4") (pintype "unspecified"))
    )
    (net (code "179") (name "unconnected-(NOR-Y4-Pad13)") (class "Default")
      (node (ref "NOR") (pin "13") (pinfunction "Y4_13") (pintype "unspecified"))
    )
    (net (code "180") (name "unconnected-(R12-Pad1)") (class "Default")
      (node (ref "R12") (pin "1") (pinfunction "1_1") (pintype "unspecified"))
    )
    (net (code "181") (name "unconnected-(SOUNDOUTPUTCOUNTER1-Q1-Pad1)") (class "Default")
      (node (ref "SOUNDOUTPUTCOUNTER1") (pin "1") (pinfunction "Q1_1") (pintype "unspecified"))
    )
    (net (code "182") (name "unconnected-(SOUNDOUTPUTCOUNTER1-Q2-Pad2)") (class "Default")
      (node (ref "SOUNDOUTPUTCOUNTER1") (pin "2") (pinfunction "Q2_2") (pintype "unspecified"))
    )
    (net (code "183") (name "unconnected-(SOUNDOUTPUTCOUNTER1-Q3-Pad3)") (class "Default")
      (node (ref "SOUNDOUTPUTCOUNTER1") (pin "3") (pinfunction "Q3_3") (pintype "unspecified"))
    )
    (net (code "184") (name "unconnected-(SOUNDOUTPUTCOUNTER1-Q4-Pad4)") (class "Default")
      (node (ref "SOUNDOUTPUTCOUNTER1") (pin "4") (pinfunction "Q4_4") (pintype "unspecified"))
    )
    (net (code "185") (name "unconnected-(SOUNDOUTPUTCOUNTER1-Q5-Pad5)") (class "Default")
      (node (ref "SOUNDOUTPUTCOUNTER1") (pin "5") (pinfunction "Q5_5") (pintype "unspecified"))
    )
    (net (code "186") (name "unconnected-(SOUNDOUTPUTCOUNTER1-Q6-Pad6)") (class "Default")
      (node (ref "SOUNDOUTPUTCOUNTER1") (pin "6") (pinfunction "Q6_6") (pintype "unspecified"))
    )
    (net (code "187") (name "unconnected-(SOUNDOUTPUTCOUNTER1-Q7-Pad7)") (class "Default")
      (node (ref "SOUNDOUTPUTCOUNTER1") (pin "7") (pinfunction "Q7_7") (pintype "unspecified"))
    )
    (net (code "188") (name "unconnected-(SOUNDOUTPUTCOUNTER1-RCO#-Pad9)") (class "Default")
      (node (ref "SOUNDOUTPUTCOUNTER1") (pin "9") (pinfunction "RCO#_9") (pintype "unspecified"))
    )
    (net (code "189") (name "unconnected-(SOUNDOUTPUTCOUNTER2-Q1-Pad1)") (class "Default")
      (node (ref "SOUNDOUTPUTCOUNTER2") (pin "1") (pinfunction "Q1_1") (pintype "unspecified"))
    )
    (net (code "190") (name "unconnected-(SOUNDOUTPUTCOUNTER2-Q2-Pad2)") (class "Default")
      (node (ref "SOUNDOUTPUTCOUNTER2") (pin "2") (pinfunction "Q2_2") (pintype "unspecified"))
    )
    (net (code "191") (name "unconnected-(SOUNDOUTPUTCOUNTER2-Q3-Pad3)") (class "Default")
      (node (ref "SOUNDOUTPUTCOUNTER2") (pin "3") (pinfunction "Q3_3") (pintype "unspecified"))
    )
    (net (code "192") (name "unconnected-(SOUNDOUTPUTCOUNTER2-Q4-Pad4)") (class "Default")
      (node (ref "SOUNDOUTPUTCOUNTER2") (pin "4") (pinfunction "Q4_4") (pintype "unspecified"))
    )
    (net (code "193") (name "unconnected-(SOUNDOUTPUTCOUNTER2-Q5-Pad5)") (class "Default")
      (node (ref "SOUNDOUTPUTCOUNTER2") (pin "5") (pinfunction "Q5_5") (pintype "unspecified"))
    )
    (net (code "194") (name "unconnected-(SOUNDOUTPUTCOUNTER2-Q6-Pad6)") (class "Default")
      (node (ref "SOUNDOUTPUTCOUNTER2") (pin "6") (pinfunction "Q6_6") (pintype "unspecified"))
    )
    (net (code "195") (name "unconnected-(SOUNDOUTPUTCOUNTER2-Q7-Pad7)") (class "Default")
      (node (ref "SOUNDOUTPUTCOUNTER2") (pin "7") (pinfunction "Q7_7") (pintype "unspecified"))
    )
    (net (code "196") (name "unconnected-(SOUNDOUTPUTCOUNTER2-RCO#-Pad9)") (class "Default")
      (node (ref "SOUNDOUTPUTCOUNTER2") (pin "9") (pinfunction "RCO#_9") (pintype "unspecified"))
    )
    (net (code "197") (name "unconnected-(U1-1A-Pad1)") (class "Default")
      (node (ref "U1") (pin "1") (pinfunction "1A_1") (pintype "unspecified"))
    )
    (net (code "198") (name "unconnected-(U1-1B-Pad2)") (class "Default")
      (node (ref "U1") (pin "2") (pinfunction "1B_2") (pintype "unspecified"))
    )
    (net (code "199") (name "unconnected-(U1-1Y-Pad3)") (class "Default")
      (node (ref "U1") (pin "3") (pinfunction "1Y_3") (pintype "unspecified"))
    )
    (net (code "200") (name "unconnected-(U1-2A-Pad4)") (class "Default")
      (node (ref "U1") (pin "4") (pinfunction "2A_4") (pintype "unspecified"))
    )
    (net (code "201") (name "unconnected-(U1-2B-Pad5)") (class "Default")
      (node (ref "U1") (pin "5") (pinfunction "2B_5") (pintype "unspecified"))
    )
    (net (code "202") (name "unconnected-(U1-2Y-Pad6)") (class "Default")
      (node (ref "U1") (pin "6") (pinfunction "2Y_6") (pintype "unspecified"))
    )
    (net (code "203") (name "unconnected-(U1-3A-Pad9)") (class "Default")
      (node (ref "U1") (pin "9") (pinfunction "3A_9") (pintype "unspecified"))
    )
    (net (code "204") (name "unconnected-(U1-3B-Pad10)") (class "Default")
      (node (ref "U1") (pin "10") (pinfunction "3B_10") (pintype "unspecified"))
    )
    (net (code "205") (name "unconnected-(U1-3Y-Pad8)") (class "Default")
      (node (ref "U1") (pin "8") (pinfunction "3Y_8") (pintype "unspecified"))
    )
    (net (code "206") (name "unconnected-(UPPERSOUNDCOUNTER1-Q4-Pad4)") (class "Default")
      (node (ref "UPPERSOUNDCOUNTER1") (pin "4") (pinfunction "Q4_4") (pintype "unspecified"))
    )
    (net (code "207") (name "unconnected-(UPPERSOUNDCOUNTER1-Q5-Pad5)") (class "Default")
      (node (ref "UPPERSOUNDCOUNTER1") (pin "5") (pinfunction "Q5_5") (pintype "unspecified"))
    )
    (net (code "208") (name "unconnected-(UPPERSOUNDCOUNTER1-Q6-Pad6)") (class "Default")
      (node (ref "UPPERSOUNDCOUNTER1") (pin "6") (pinfunction "Q6_6") (pintype "unspecified"))
    )
    (net (code "209") (name "unconnected-(UPPERSOUNDCOUNTER1-Q7-Pad7)") (class "Default")
      (node (ref "UPPERSOUNDCOUNTER1") (pin "7") (pinfunction "Q7_7") (pintype "unspecified"))
    )
    (net (code "210") (name "unconnected-(UPPERSOUNDCOUNTER1-RCO#-Pad9)") (class "Default")
      (node (ref "UPPERSOUNDCOUNTER1") (pin "9") (pinfunction "RCO#_9") (pintype "unspecified"))
    )
    (net (code "211") (name "unconnected-(UPPERSOUNDCOUNTER2-Q4-Pad4)") (class "Default")
      (node (ref "UPPERSOUNDCOUNTER2") (pin "4") (pinfunction "Q4_4") (pintype "unspecified"))
    )
    (net (code "212") (name "unconnected-(UPPERSOUNDCOUNTER2-Q5-Pad5)") (class "Default")
      (node (ref "UPPERSOUNDCOUNTER2") (pin "5") (pinfunction "Q5_5") (pintype "unspecified"))
    )
    (net (code "213") (name "unconnected-(UPPERSOUNDCOUNTER2-Q6-Pad6)") (class "Default")
      (node (ref "UPPERSOUNDCOUNTER2") (pin "6") (pinfunction "Q6_6") (pintype "unspecified"))
    )
    (net (code "214") (name "unconnected-(UPPERSOUNDCOUNTER2-Q7-Pad7)") (class "Default")
      (node (ref "UPPERSOUNDCOUNTER2") (pin "7") (pinfunction "Q7_7") (pintype "unspecified"))
    )
    (net (code "215") (name "unconnected-(UPPERSOUNDCOUNTER2-RCO#-Pad9)") (class "Default")
      (node (ref "UPPERSOUNDCOUNTER2") (pin "9") (pinfunction "RCO#_9") (pintype "unspecified"))
    )
  )
)
